# Dist_board__1_21.net
KiCad netlist of a schematic drawn in EAGLE
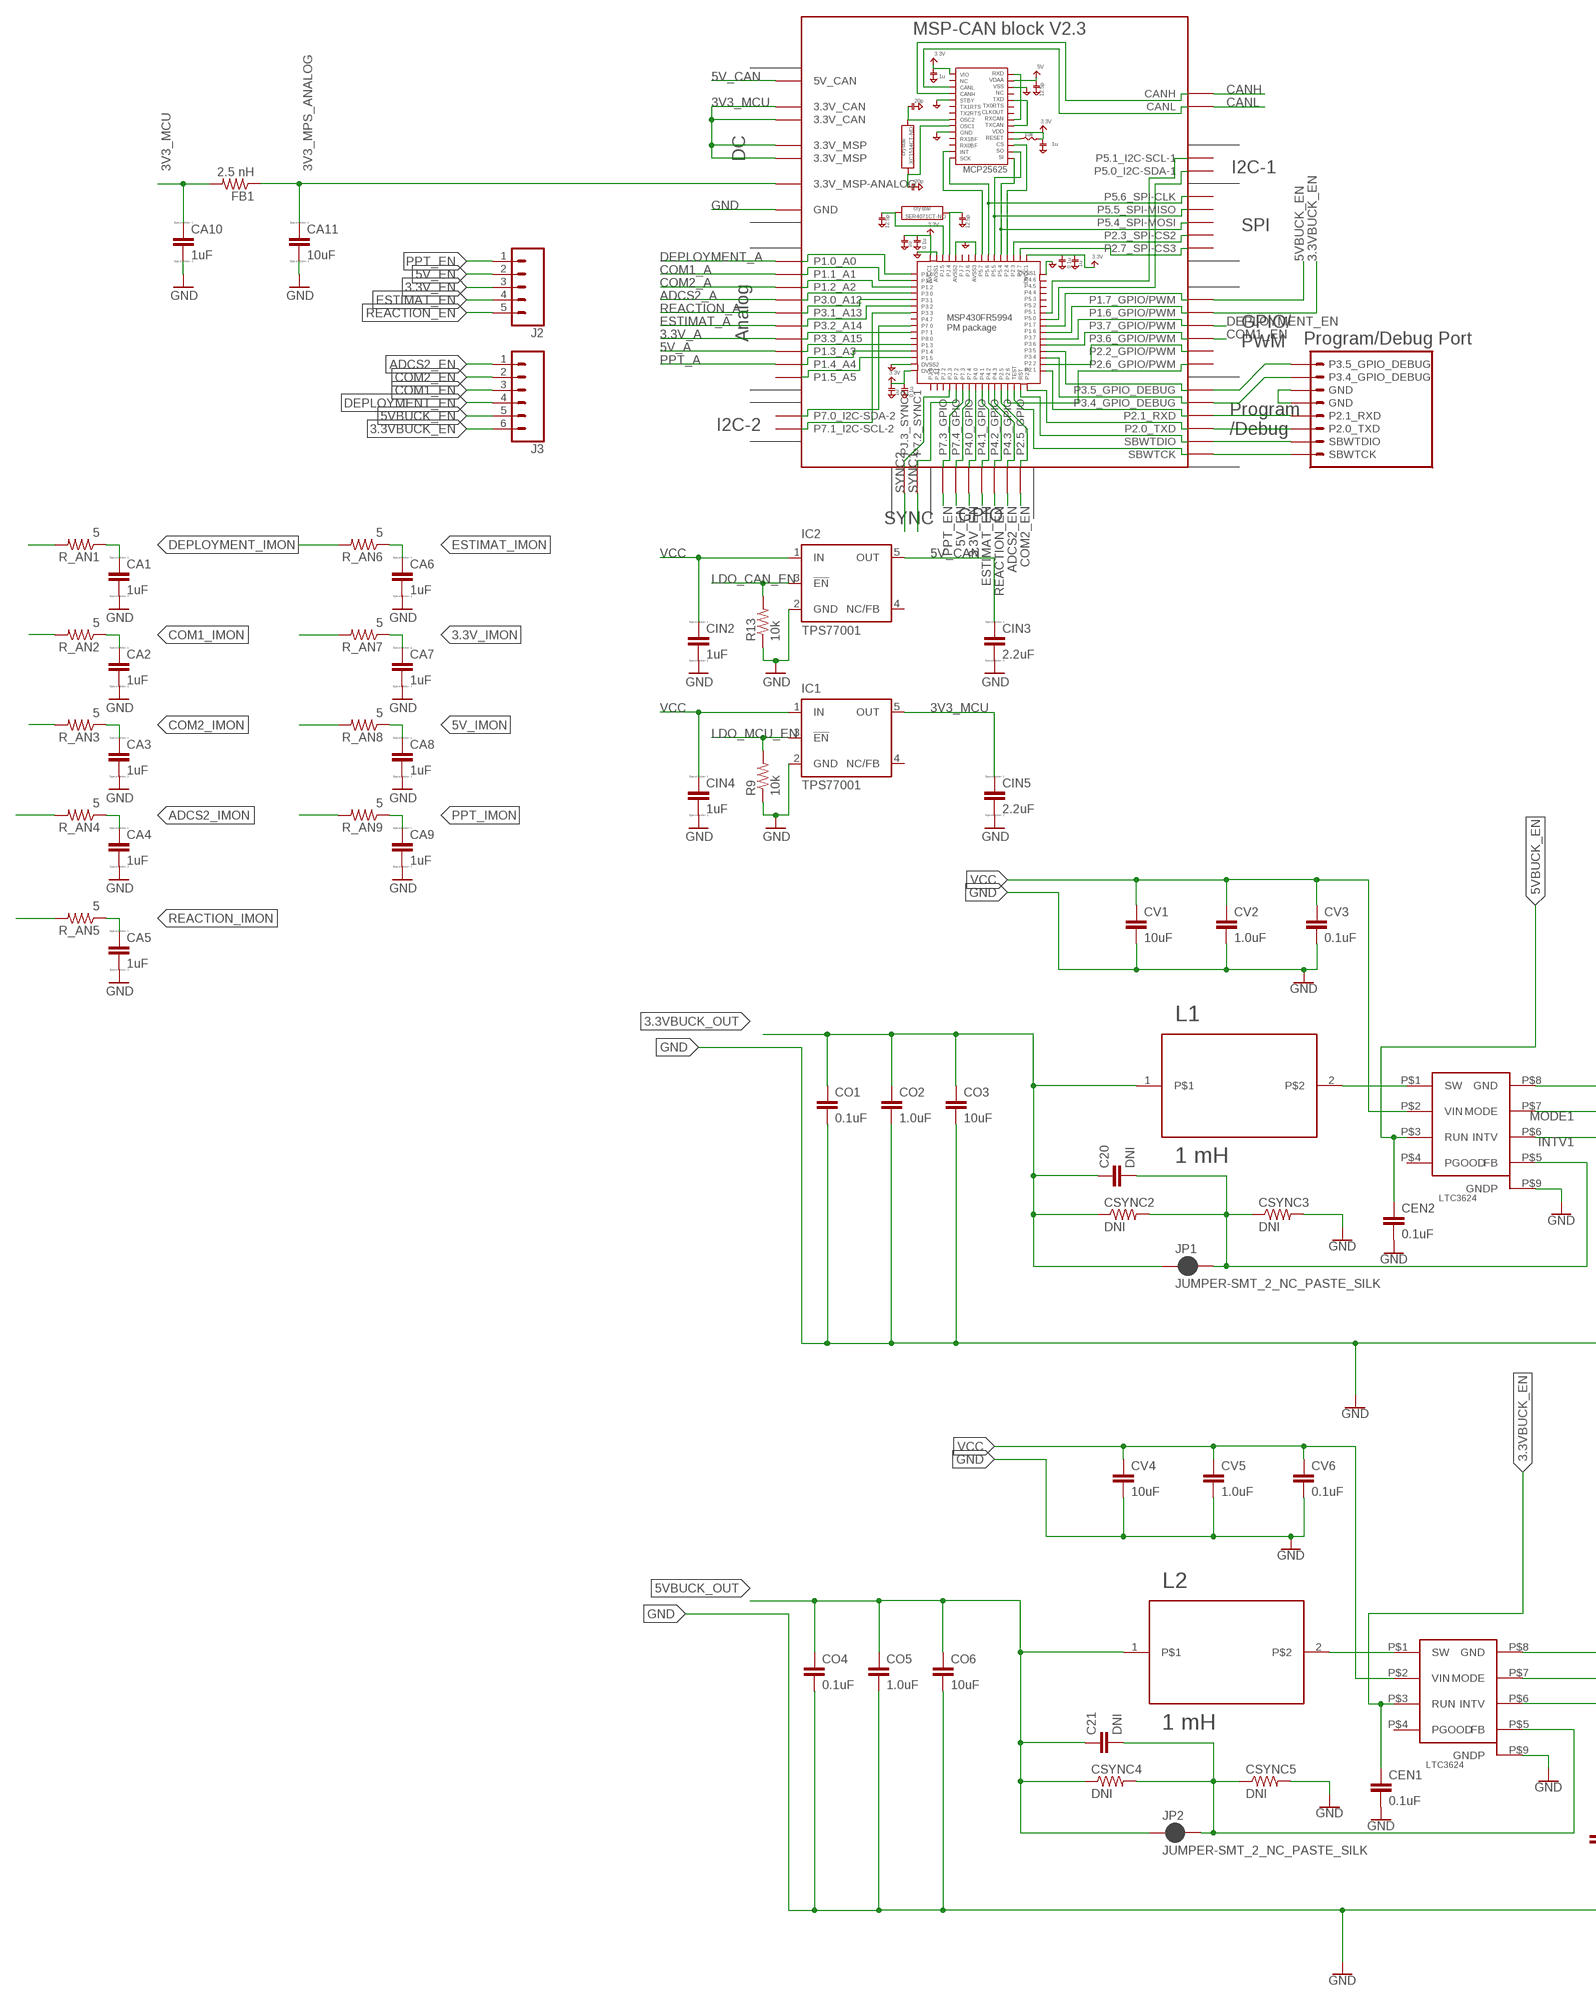
[diagram p0: schematic, sheet 1, part 1 of 3]
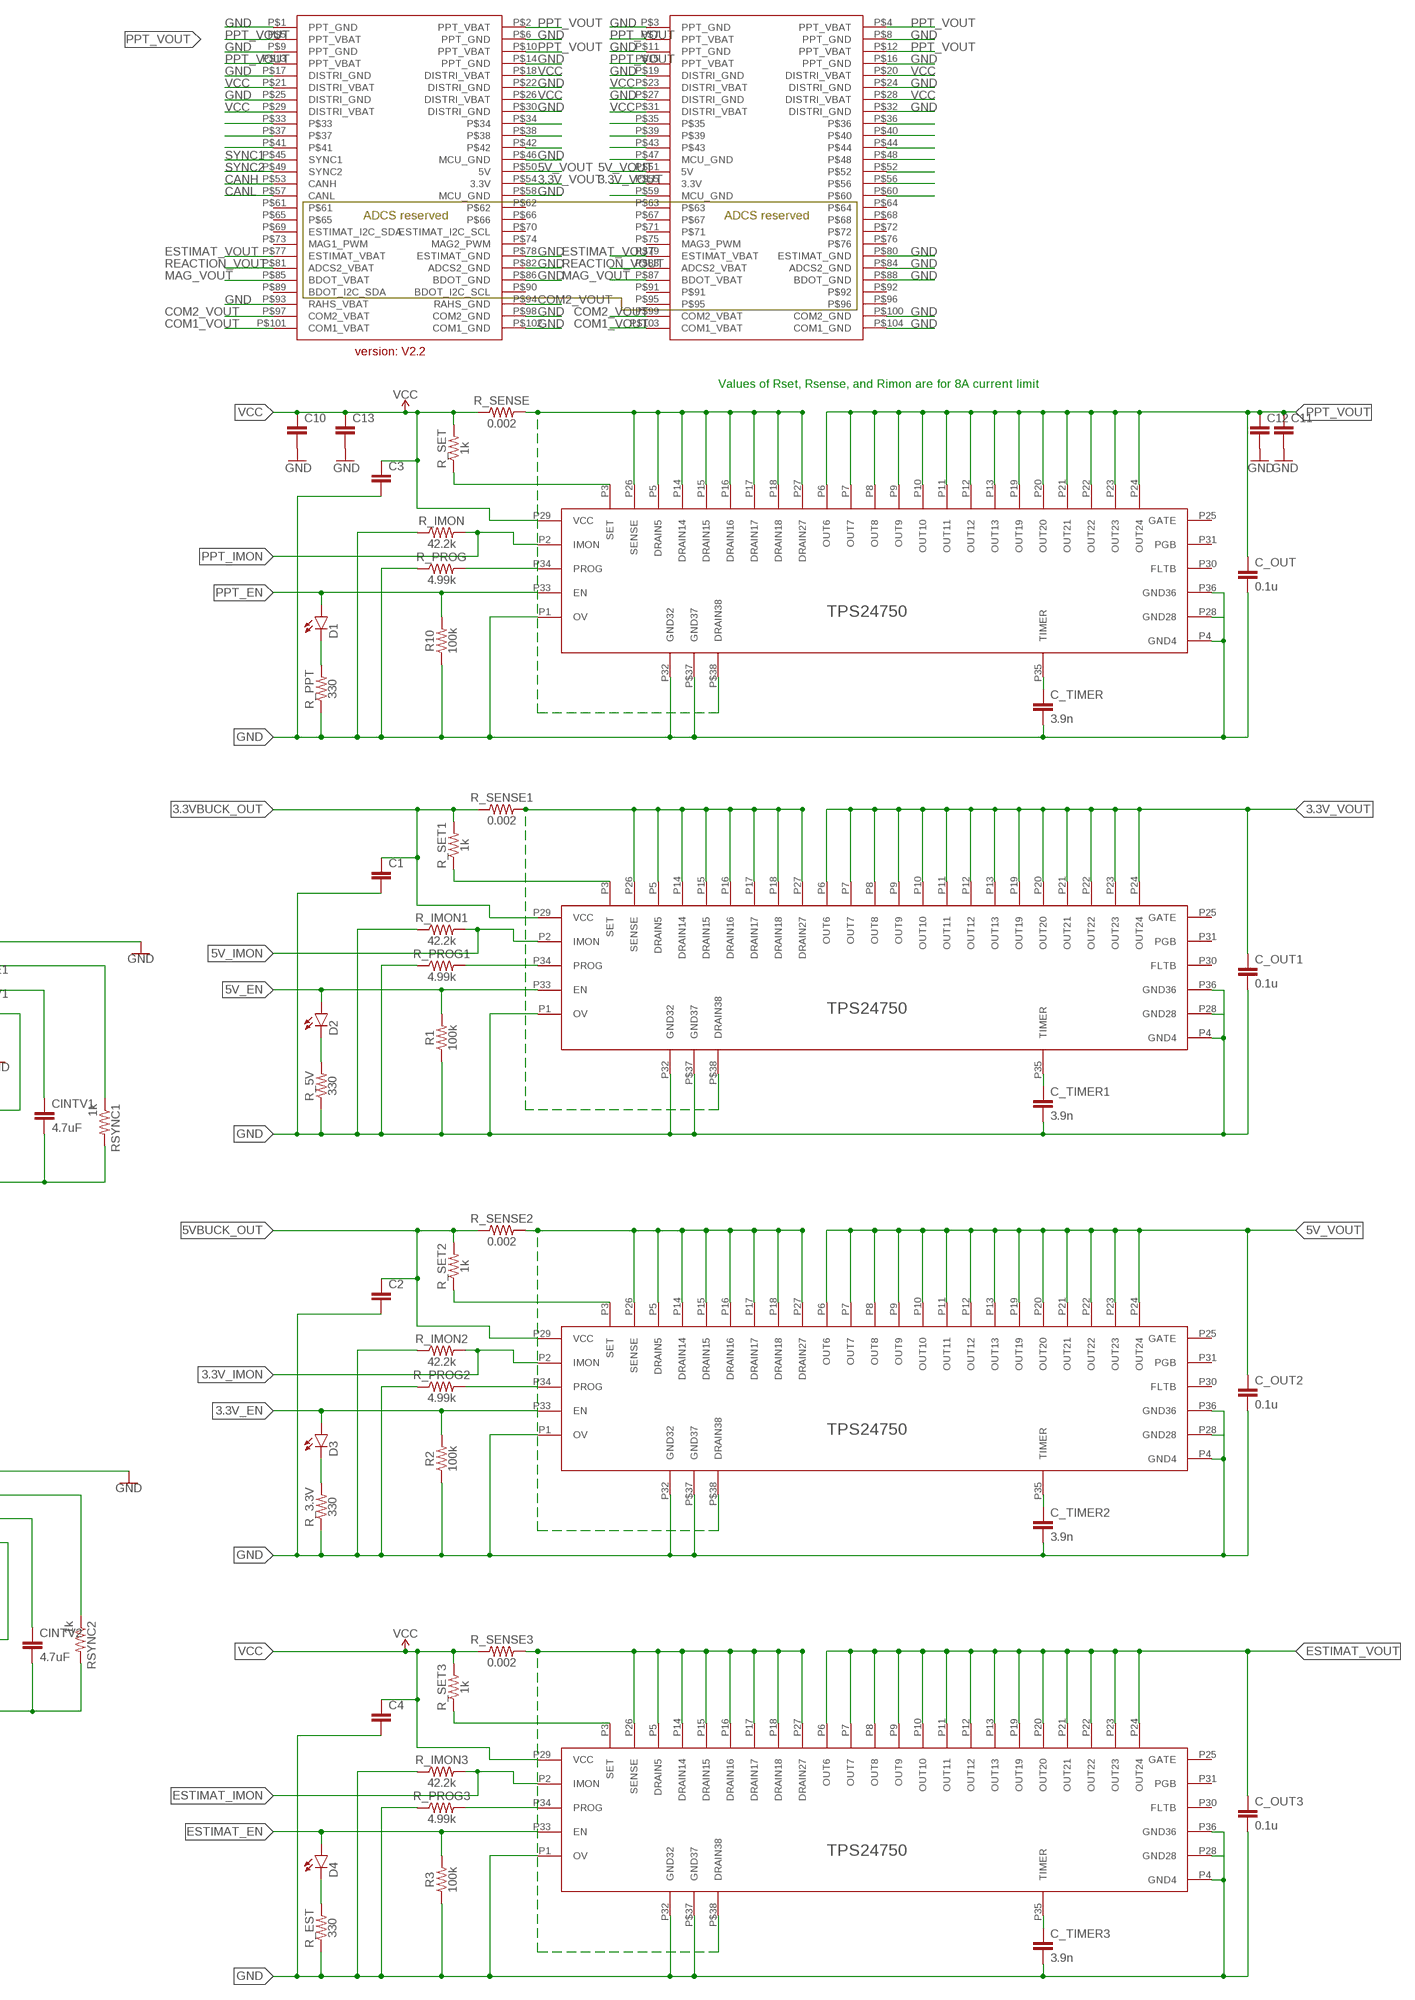
[diagram p1: schematic, sheet 1, part 2 of 3]
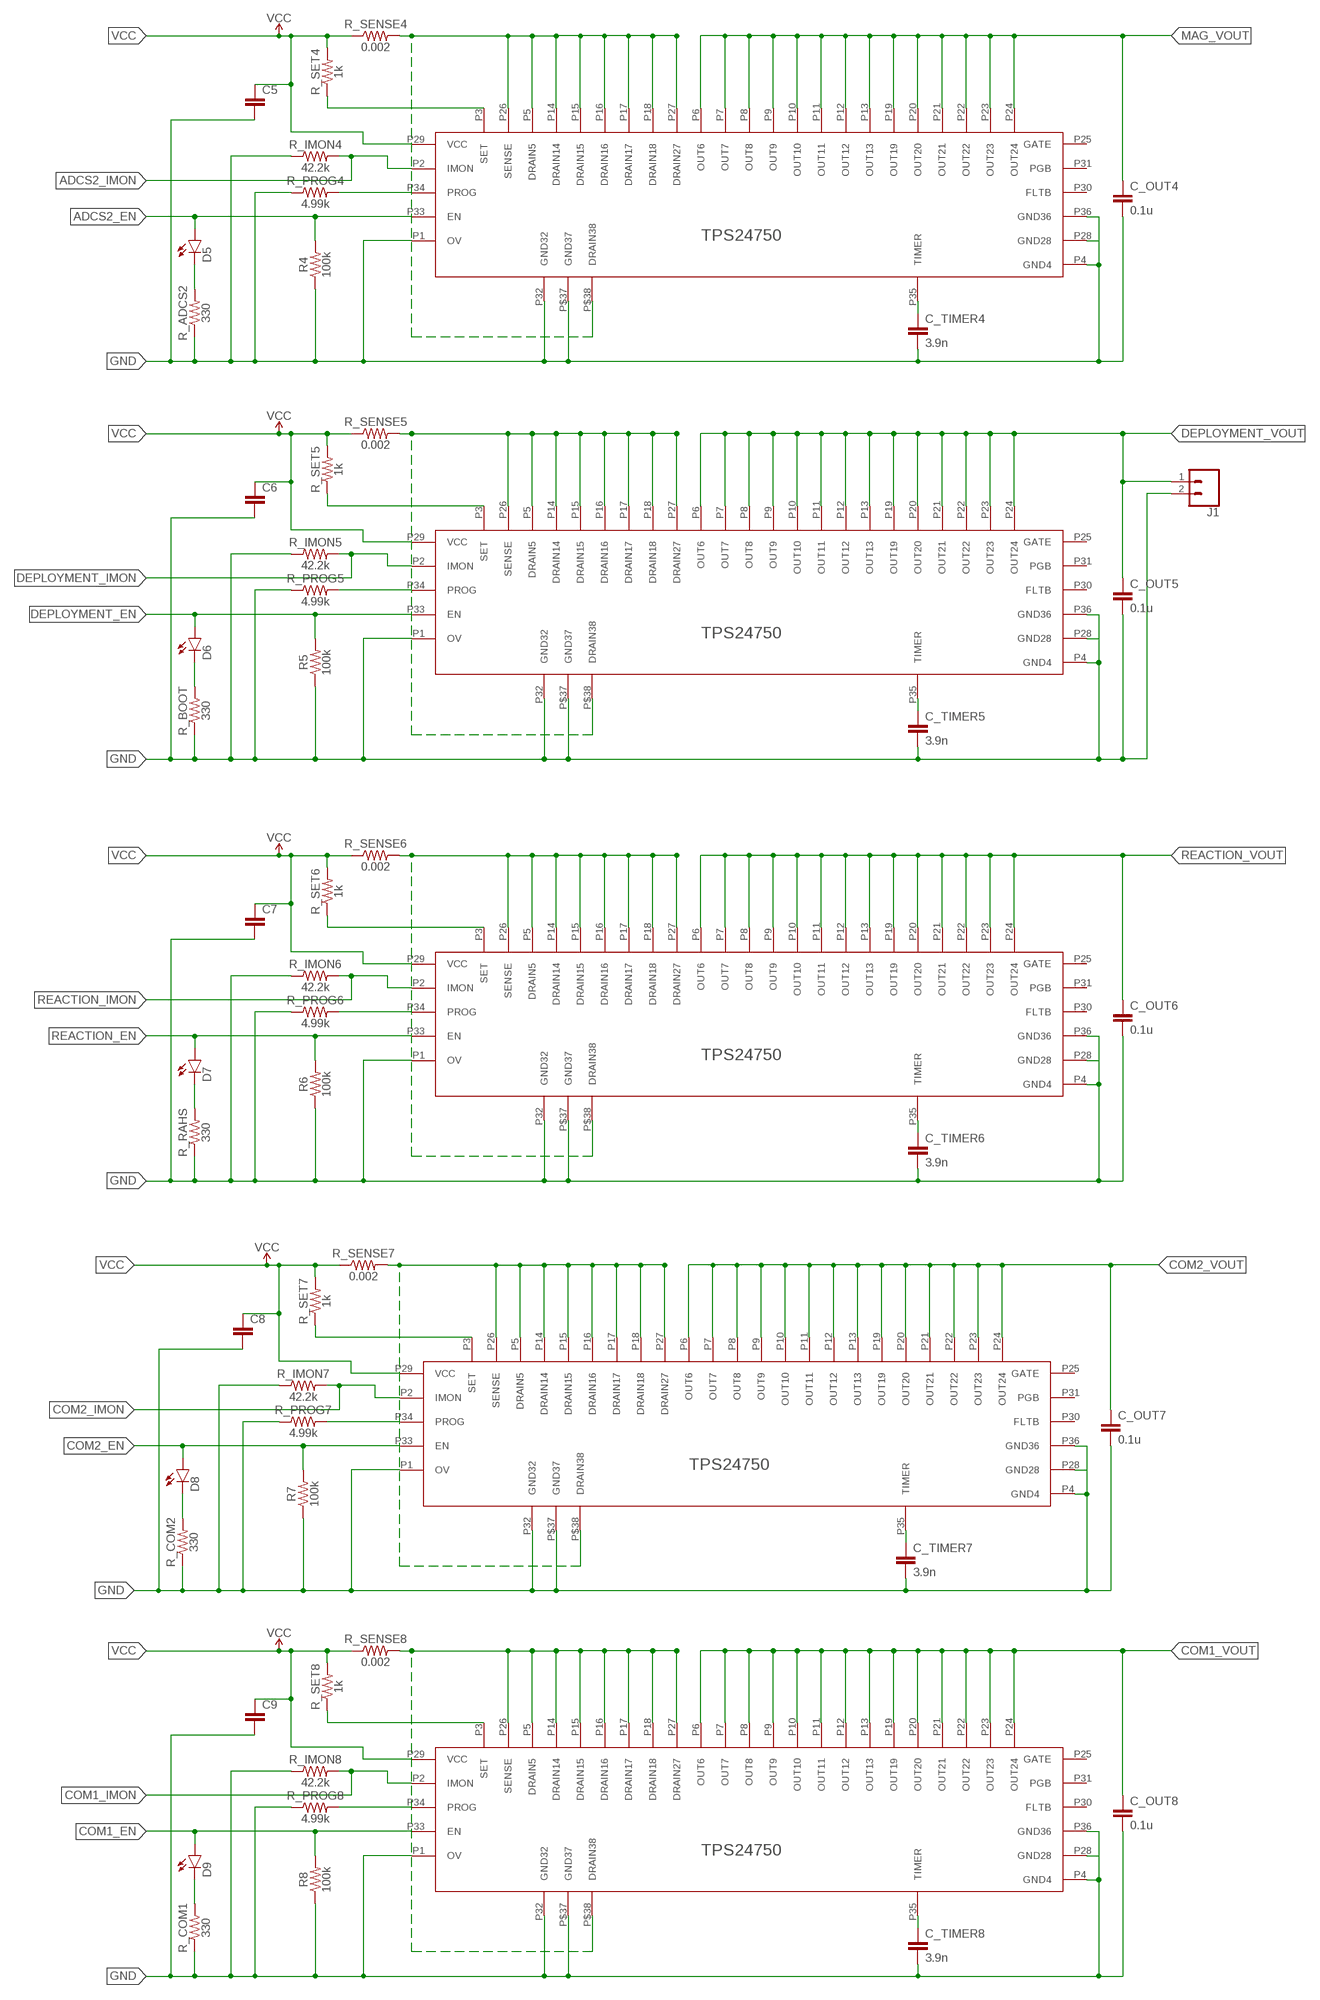
[diagram p2: schematic, sheet 1, part 3 of 3]

(export (version "E")
  (design (tool "Eeschema 10.0.6"))
  (components
    (comp (ref "C1")
      (value "GEN_CAP_0805SMD")
      (footprint "eagle-import:0805")
      (libsource (lib "eagle-import") (part "GEN_CAP_0805SMD"))
    )
    (comp (ref "C2")
      (value "GEN_CAP_0805SMD")
      (footprint "eagle-import:0805")
      (libsource (lib "eagle-import") (part "GEN_CAP_0805SMD"))
    )
    (comp (ref "C3")
      (value "GEN_CAP_0805SMD")
      (footprint "eagle-import:0805")
      (libsource (lib "eagle-import") (part "GEN_CAP_0805SMD"))
    )
    (comp (ref "C4")
      (value "GEN_CAP_0805SMD")
      (footprint "eagle-import:0805")
      (libsource (lib "eagle-import") (part "GEN_CAP_0805SMD"))
    )
    (comp (ref "C5")
      (value "GEN_CAP_0805SMD")
      (footprint "eagle-import:0805")
      (libsource (lib "eagle-import") (part "GEN_CAP_0805SMD"))
    )
    (comp (ref "C6")
      (value "GEN_CAP_0805SMD")
      (footprint "eagle-import:0805")
      (libsource (lib "eagle-import") (part "GEN_CAP_0805SMD"))
    )
    (comp (ref "C7")
      (value "GEN_CAP_0805SMD")
      (footprint "eagle-import:0805")
      (libsource (lib "eagle-import") (part "GEN_CAP_0805SMD"))
    )
    (comp (ref "C8")
      (value "GEN_CAP_0805SMD")
      (footprint "eagle-import:0805")
      (libsource (lib "eagle-import") (part "GEN_CAP_0805SMD"))
    )
    (comp (ref "C9")
      (value "GEN_CAP_0805SMD")
      (footprint "eagle-import:0805")
      (libsource (lib "eagle-import") (part "GEN_CAP_0805SMD"))
    )
    (comp (ref "C10")
      (value "GEN_CAP_0805SMD")
      (footprint "eagle-import:0805")
      (libsource (lib "eagle-import") (part "GEN_CAP_0805SMD"))
    )
    (comp (ref "C11")
      (value "GEN_CAP_0805SMD")
      (footprint "eagle-import:0805")
      (libsource (lib "eagle-import") (part "GEN_CAP_0805SMD"))
    )
    (comp (ref "C12")
      (value "GEN_CAP_0805SMD")
      (footprint "eagle-import:0805")
      (libsource (lib "eagle-import") (part "GEN_CAP_0805SMD"))
    )
    (comp (ref "C13")
      (value "GEN_CAP_0805SMD")
      (footprint "eagle-import:0805")
      (libsource (lib "eagle-import") (part "GEN_CAP_0805SMD"))
    )
    (comp (ref "C20")
      (value "DNI")
      (footprint "eagle-import:0805")
      (libsource (lib "eagle-import") (part "1.0UF-0805-25V-(+80/-20%)"))
    )
    (comp (ref "C21")
      (value "DNI")
      (footprint "eagle-import:0805")
      (libsource (lib "eagle-import") (part "1.0UF-0805-25V-(+80/-20%)"))
    )
    (comp (ref "CA1")
      (value "1uF")
      (footprint "eagle-import:C0805")
      (libsource (lib "eagle-import") (part "C"))
    )
    (comp (ref "CA2")
      (value "1uF")
      (footprint "eagle-import:C0805")
      (libsource (lib "eagle-import") (part "C"))
    )
    (comp (ref "CA3")
      (value "1uF")
      (footprint "eagle-import:C0805")
      (libsource (lib "eagle-import") (part "C"))
    )
    (comp (ref "CA4")
      (value "1uF")
      (footprint "eagle-import:C0805")
      (libsource (lib "eagle-import") (part "C"))
    )
    (comp (ref "CA5")
      (value "1uF")
      (footprint "eagle-import:C0805")
      (libsource (lib "eagle-import") (part "C"))
    )
    (comp (ref "CA6")
      (value "1uF")
      (footprint "eagle-import:C0805")
      (libsource (lib "eagle-import") (part "C"))
    )
    (comp (ref "CA7")
      (value "1uF")
      (footprint "eagle-import:C0805")
      (libsource (lib "eagle-import") (part "C"))
    )
    (comp (ref "CA8")
      (value "1uF")
      (footprint "eagle-import:C0805")
      (libsource (lib "eagle-import") (part "C"))
    )
    (comp (ref "CA9")
      (value "1uF")
      (footprint "eagle-import:C0805")
      (libsource (lib "eagle-import") (part "C"))
    )
    (comp (ref "CA10")
      (value "1uF")
      (footprint "eagle-import:C0805")
      (libsource (lib "eagle-import") (part "C"))
    )
    (comp (ref "CA11")
      (value "10uF")
      (footprint "eagle-import:C0805")
      (libsource (lib "eagle-import") (part "C"))
    )
    (comp (ref "CEN1")
      (value "0.1uF")
      (footprint "eagle-import:0805")
      (libsource (lib "eagle-import") (part "2.2UF-0805-25V-(+80/-20%)"))
    )
    (comp (ref "CEN2")
      (value "0.1uF")
      (footprint "eagle-import:0805")
      (libsource (lib "eagle-import") (part "2.2UF-0805-25V-(+80/-20%)"))
    )
    (comp (ref "CIN2")
      (value "1uF")
      (footprint "eagle-import:C0805")
      (libsource (lib "eagle-import") (part "C"))
    )
    (comp (ref "CIN3")
      (value "2.2uF")
      (footprint "eagle-import:C0805")
      (libsource (lib "eagle-import") (part "C"))
    )
    (comp (ref "CIN4")
      (value "1uF")
      (footprint "eagle-import:C0805")
      (libsource (lib "eagle-import") (part "C"))
    )
    (comp (ref "CIN5")
      (value "2.2uF")
      (footprint "eagle-import:C0805")
      (libsource (lib "eagle-import") (part "C"))
    )
    (comp (ref "CINTV1")
      (value "4.7uF")
      (footprint "eagle-import:0805")
      (libsource (lib "eagle-import") (part "2.2UF-0805-25V-(+80/-20%)"))
    )
    (comp (ref "CINTV2")
      (value "4.7uF")
      (footprint "eagle-import:0805")
      (libsource (lib "eagle-import") (part "2.2UF-0805-25V-(+80/-20%)"))
    )
    (comp (ref "CO1")
      (value "0.1uF")
      (footprint "eagle-import:0805")
      (libsource (lib "eagle-import") (part "1.0UF-0805-25V-(+80/-20%)"))
    )
    (comp (ref "CO2")
      (value "1.0uF")
      (footprint "eagle-import:0805")
      (libsource (lib "eagle-import") (part "1.0UF-0805-25V-(+80/-20%)"))
    )
    (comp (ref "CO3")
      (value "10uF")
      (footprint "eagle-import:0805")
      (libsource (lib "eagle-import") (part "10UF-0805-10V-10%"))
    )
    (comp (ref "CO4")
      (value "0.1uF")
      (footprint "eagle-import:0805")
      (libsource (lib "eagle-import") (part "1.0UF-0805-25V-(+80/-20%)"))
    )
    (comp (ref "CO5")
      (value "1.0uF")
      (footprint "eagle-import:0805")
      (libsource (lib "eagle-import") (part "1.0UF-0805-25V-(+80/-20%)"))
    )
    (comp (ref "CO6")
      (value "10uF")
      (footprint "eagle-import:0805")
      (libsource (lib "eagle-import") (part "10UF-0805-10V-10%"))
    )
    (comp (ref "CSYNC2")
      (value "DNI")
      (footprint "eagle-import:R0805")
      (libsource (lib "eagle-import") (part "R-US_R0805"))
    )
    (comp (ref "CSYNC3")
      (value "DNI")
      (footprint "eagle-import:R0805")
      (libsource (lib "eagle-import") (part "R-US_R0805"))
    )
    (comp (ref "CSYNC4")
      (value "DNI")
      (footprint "eagle-import:R0805")
      (libsource (lib "eagle-import") (part "R-US_R0805"))
    )
    (comp (ref "CSYNC5")
      (value "DNI")
      (footprint "eagle-import:R0805")
      (libsource (lib "eagle-import") (part "R-US_R0805"))
    )
    (comp (ref "CV1")
      (value "10uF")
      (footprint "eagle-import:0805")
      (libsource (lib "eagle-import") (part "1.0UF-0805-25V-10%"))
    )
    (comp (ref "CV2")
      (value "1.0uF")
      (footprint "eagle-import:0805")
      (libsource (lib "eagle-import") (part "1.0UF-0805-25V-10%"))
    )
    (comp (ref "CV3")
      (value "0.1uF")
      (footprint "eagle-import:0805")
      (libsource (lib "eagle-import") (part "1.0UF-0805-25V-10%"))
    )
    (comp (ref "CV4")
      (value "10uF")
      (footprint "eagle-import:0805")
      (libsource (lib "eagle-import") (part "1.0UF-0805-25V-10%"))
    )
    (comp (ref "CV5")
      (value "1.0uF")
      (footprint "eagle-import:0805")
      (libsource (lib "eagle-import") (part "1.0UF-0805-25V-10%"))
    )
    (comp (ref "CV6")
      (value "0.1uF")
      (footprint "eagle-import:0805")
      (libsource (lib "eagle-import") (part "1.0UF-0805-25V-10%"))
    )
    (comp (ref "C_OUT")
      (value "0.1u")
      (footprint "eagle-import:0805")
      (libsource (lib "eagle-import") (part "GEN_CAP_0805SMD"))
    )
    (comp (ref "C_OUT1")
      (value "0.1u")
      (footprint "eagle-import:0805")
      (libsource (lib "eagle-import") (part "GEN_CAP_0805SMD"))
    )
    (comp (ref "C_OUT2")
      (value "0.1u")
      (footprint "eagle-import:0805")
      (libsource (lib "eagle-import") (part "GEN_CAP_0805SMD"))
    )
    (comp (ref "C_OUT3")
      (value "0.1u")
      (footprint "eagle-import:0805")
      (libsource (lib "eagle-import") (part "GEN_CAP_0805SMD"))
    )
    (comp (ref "C_OUT4")
      (value "0.1u")
      (footprint "eagle-import:0805")
      (libsource (lib "eagle-import") (part "GEN_CAP_0805SMD"))
    )
    (comp (ref "C_OUT5")
      (value "0.1u")
      (footprint "eagle-import:0805")
      (libsource (lib "eagle-import") (part "GEN_CAP_0805SMD"))
    )
    (comp (ref "C_OUT6")
      (value "0.1u")
      (footprint "eagle-import:0805")
      (libsource (lib "eagle-import") (part "GEN_CAP_0805SMD"))
    )
    (comp (ref "C_OUT7")
      (value "0.1u")
      (footprint "eagle-import:0805")
      (libsource (lib "eagle-import") (part "GEN_CAP_0805SMD"))
    )
    (comp (ref "C_OUT8")
      (value "0.1u")
      (footprint "eagle-import:0805")
      (libsource (lib "eagle-import") (part "GEN_CAP_0805SMD"))
    )
    (comp (ref "C_TIMER")
      (value "3.9n")
      (footprint "eagle-import:0805")
      (libsource (lib "eagle-import") (part "GEN_CAP_0805SMD"))
    )
    (comp (ref "C_TIMER1")
      (value "3.9n")
      (footprint "eagle-import:0805")
      (libsource (lib "eagle-import") (part "GEN_CAP_0805SMD"))
    )
    (comp (ref "C_TIMER2")
      (value "3.9n")
      (footprint "eagle-import:0805")
      (libsource (lib "eagle-import") (part "GEN_CAP_0805SMD"))
    )
    (comp (ref "C_TIMER3")
      (value "3.9n")
      (footprint "eagle-import:0805")
      (libsource (lib "eagle-import") (part "GEN_CAP_0805SMD"))
    )
    (comp (ref "C_TIMER4")
      (value "3.9n")
      (footprint "eagle-import:0805")
      (libsource (lib "eagle-import") (part "GEN_CAP_0805SMD"))
    )
    (comp (ref "C_TIMER5")
      (value "3.9n")
      (footprint "eagle-import:0805")
      (libsource (lib "eagle-import") (part "GEN_CAP_0805SMD"))
    )
    (comp (ref "C_TIMER6")
      (value "3.9n")
      (footprint "eagle-import:0805")
      (libsource (lib "eagle-import") (part "GEN_CAP_0805SMD"))
    )
    (comp (ref "C_TIMER7")
      (value "3.9n")
      (footprint "eagle-import:0805")
      (libsource (lib "eagle-import") (part "GEN_CAP_0805SMD"))
    )
    (comp (ref "C_TIMER8")
      (value "3.9n")
      (footprint "eagle-import:0805")
      (libsource (lib "eagle-import") (part "GEN_CAP_0805SMD"))
    )
    (comp (ref "D1")
      (value "LED")
      (footprint "eagle-import:LED-1206")
      (libsource (lib "eagle-import") (part "LED"))
    )
    (comp (ref "D2")
      (value "LED")
      (footprint "eagle-import:LED-1206")
      (libsource (lib "eagle-import") (part "LED"))
    )
    (comp (ref "D3")
      (value "LED")
      (footprint "eagle-import:LED-1206")
      (libsource (lib "eagle-import") (part "LED"))
    )
    (comp (ref "D4")
      (value "LED")
      (footprint "eagle-import:LED-1206")
      (libsource (lib "eagle-import") (part "LED"))
    )
    (comp (ref "D5")
      (value "LED")
      (footprint "eagle-import:LED-1206")
      (libsource (lib "eagle-import") (part "LED"))
    )
    (comp (ref "D6")
      (value "LED")
      (footprint "eagle-import:LED-1206")
      (libsource (lib "eagle-import") (part "LED"))
    )
    (comp (ref "D7")
      (value "LED")
      (footprint "eagle-import:LED-1206")
      (libsource (lib "eagle-import") (part "LED"))
    )
    (comp (ref "D8")
      (value "LED")
      (footprint "eagle-import:LED-1206")
      (libsource (lib "eagle-import") (part "LED"))
    )
    (comp (ref "D9")
      (value "LED")
      (footprint "eagle-import:LED-1206")
      (libsource (lib "eagle-import") (part "LED"))
    )
    (comp (ref "FB1")
      (value "2.5 nH")
      (footprint "eagle-import:R0805")
      (libsource (lib "eagle-import") (part "R-US_R0805"))
    )
    (comp (ref "IC1")
      (value "TPS77001")
      (footprint "eagle-import:SOT23-DBV")
      (fields (field (name "MF") "TEXAS INSTRUMENTS") (field (name "MPN") "TPS77001DBVT"))
      (libsource (lib "eagle-import") (part "TPS77001"))
    )
    (comp (ref "IC2")
      (value "TPS77001")
      (footprint "eagle-import:SOT23-DBV")
      (fields (field (name "MF") "TEXAS INSTRUMENTS") (field (name "MPN") "TPS77001DBVT"))
      (libsource (lib "eagle-import") (part "TPS77001"))
    )
    (comp (ref "J1")
      (value "CONN_023.5MM")
      (footprint "eagle-import:SCREWTERMINAL-3.5MM-2")
      (libsource (lib "eagle-import") (part "CONN_023.5MM"))
    )
    (comp (ref "J2")
      (value "CONN_05LOCK")
      (footprint "eagle-import:1X05_LOCK")
      (libsource (lib "eagle-import") (part "CONN_05LOCK"))
    )
    (comp (ref "J3")
      (value "CONN_06LOCK")
      (footprint "eagle-import:1X06_LOCK")
      (libsource (lib "eagle-import") (part "CONN_06LOCK"))
    )
    (comp (ref "JP1")
      (value "JUMPER-SMT_2_NC_PASTE_SILK")
      (footprint "eagle-import:SMT-JUMPER_2_NC_PASTE_SILK")
      (libsource (lib "eagle-import") (part "JUMPER-SMT_2_NC_PASTE_SILK"))
    )
    (comp (ref "JP2")
      (value "JUMPER-SMT_2_NC_PASTE_SILK")
      (footprint "eagle-import:SMT-JUMPER_2_NC_PASTE_SILK")
      (libsource (lib "eagle-import") (part "JUMPER-SMT_2_NC_PASTE_SILK"))
    )
    (comp (ref "L1")
      (value "1 mH")
      (footprint "eagle-import:COILCRAFT")
      (libsource (lib "eagle-import") (part "XAL4030-332ME"))
    )
    (comp (ref "L2")
      (value "1 mH")
      (footprint "eagle-import:COILCRAFT")
      (libsource (lib "eagle-import") (part "XAL4030-332ME"))
    )
    (comp (ref "R1")
      (value "100k")
      (footprint "eagle-import:0805")
      (libsource (lib "eagle-import") (part "GEN_RES_0805SMD"))
    )
    (comp (ref "R2")
      (value "100k")
      (footprint "eagle-import:0805")
      (libsource (lib "eagle-import") (part "GEN_RES_0805SMD"))
    )
    (comp (ref "R3")
      (value "100k")
      (footprint "eagle-import:0805")
      (libsource (lib "eagle-import") (part "GEN_RES_0805SMD"))
    )
    (comp (ref "R4")
      (value "100k")
      (footprint "eagle-import:0805")
      (libsource (lib "eagle-import") (part "GEN_RES_0805SMD"))
    )
    (comp (ref "R5")
      (value "100k")
      (footprint "eagle-import:0805")
      (libsource (lib "eagle-import") (part "GEN_RES_0805SMD"))
    )
    (comp (ref "R6")
      (value "100k")
      (footprint "eagle-import:0805")
      (libsource (lib "eagle-import") (part "GEN_RES_0805SMD"))
    )
    (comp (ref "R7")
      (value "100k")
      (footprint "eagle-import:0805")
      (libsource (lib "eagle-import") (part "GEN_RES_0805SMD"))
    )
    (comp (ref "R8")
      (value "100k")
      (footprint "eagle-import:0805")
      (libsource (lib "eagle-import") (part "GEN_RES_0805SMD"))
    )
    (comp (ref "R9")
      (value "10k")
      (footprint "eagle-import:R0805")
      (libsource (lib "eagle-import") (part "R-US_R0805"))
    )
    (comp (ref "R10")
      (value "100k")
      (footprint "eagle-import:0805")
      (libsource (lib "eagle-import") (part "GEN_RES_0805SMD"))
    )
    (comp (ref "R13")
      (value "10k")
      (footprint "eagle-import:R0805")
      (libsource (lib "eagle-import") (part "R-US_R0805"))
    )
    (comp (ref "RSYNC1")
      (value "1k")
      (footprint "eagle-import:R0805")
      (libsource (lib "eagle-import") (part "R-US_R0805"))
    )
    (comp (ref "RSYNC2")
      (value "1k")
      (footprint "eagle-import:R0805")
      (libsource (lib "eagle-import") (part "R-US_R0805"))
    )
    (comp (ref "R_3.3V")
      (value "330")
      (footprint "eagle-import:0805")
      (libsource (lib "eagle-import") (part "GEN_RES_0805SMD"))
    )
    (comp (ref "R_5V")
      (value "330")
      (footprint "eagle-import:0805")
      (libsource (lib "eagle-import") (part "GEN_RES_0805SMD"))
    )
    (comp (ref "R_ADCS2")
      (value "330")
      (footprint "eagle-import:0805")
      (libsource (lib "eagle-import") (part "GEN_RES_0805SMD"))
    )
    (comp (ref "R_AN1")
      (value "5")
      (footprint "eagle-import:R0805")
      (libsource (lib "eagle-import") (part "R-US_R0805"))
    )
    (comp (ref "R_AN2")
      (value "5")
      (footprint "eagle-import:R0805")
      (libsource (lib "eagle-import") (part "R-US_R0805"))
    )
    (comp (ref "R_AN3")
      (value "5")
      (footprint "eagle-import:R0805")
      (libsource (lib "eagle-import") (part "R-US_R0805"))
    )
    (comp (ref "R_AN4")
      (value "5")
      (footprint "eagle-import:R0805")
      (libsource (lib "eagle-import") (part "R-US_R0805"))
    )
    (comp (ref "R_AN5")
      (value "5")
      (footprint "eagle-import:R0805")
      (libsource (lib "eagle-import") (part "R-US_R0805"))
    )
    (comp (ref "R_AN6")
      (value "5")
      (footprint "eagle-import:R0805")
      (libsource (lib "eagle-import") (part "R-US_R0805"))
    )
    (comp (ref "R_AN7")
      (value "5")
      (footprint "eagle-import:R0805")
      (libsource (lib "eagle-import") (part "R-US_R0805"))
    )
    (comp (ref "R_AN8")
      (value "5")
      (footprint "eagle-import:R0805")
      (libsource (lib "eagle-import") (part "R-US_R0805"))
    )
    (comp (ref "R_AN9")
      (value "5")
      (footprint "eagle-import:R0805")
      (libsource (lib "eagle-import") (part "R-US_R0805"))
    )
    (comp (ref "R_BOOT")
      (value "330")
      (footprint "eagle-import:0805")
      (libsource (lib "eagle-import") (part "GEN_RES_0805SMD"))
    )
    (comp (ref "R_COM1")
      (value "330")
      (footprint "eagle-import:0805")
      (libsource (lib "eagle-import") (part "GEN_RES_0805SMD"))
    )
    (comp (ref "R_COM2")
      (value "330")
      (footprint "eagle-import:0805")
      (libsource (lib "eagle-import") (part "GEN_RES_0805SMD"))
    )
    (comp (ref "R_EST")
      (value "330")
      (footprint "eagle-import:0805")
      (libsource (lib "eagle-import") (part "GEN_RES_0805SMD"))
    )
    (comp (ref "R_IMON")
      (value "42.2k")
      (footprint "eagle-import:0805")
      (libsource (lib "eagle-import") (part "GEN_RES_0805SMD"))
    )
    (comp (ref "R_IMON1")
      (value "42.2k")
      (footprint "eagle-import:0805")
      (libsource (lib "eagle-import") (part "GEN_RES_0805SMD"))
    )
    (comp (ref "R_IMON2")
      (value "42.2k")
      (footprint "eagle-import:0805")
      (libsource (lib "eagle-import") (part "GEN_RES_0805SMD"))
    )
    (comp (ref "R_IMON3")
      (value "42.2k")
      (footprint "eagle-import:0805")
      (libsource (lib "eagle-import") (part "GEN_RES_0805SMD"))
    )
    (comp (ref "R_IMON4")
      (value "42.2k")
      (footprint "eagle-import:0805")
      (libsource (lib "eagle-import") (part "GEN_RES_0805SMD"))
    )
    (comp (ref "R_IMON5")
      (value "42.2k")
      (footprint "eagle-import:0805")
      (libsource (lib "eagle-import") (part "GEN_RES_0805SMD"))
    )
    (comp (ref "R_IMON6")
      (value "42.2k")
      (footprint "eagle-import:0805")
      (libsource (lib "eagle-import") (part "GEN_RES_0805SMD"))
    )
    (comp (ref "R_IMON7")
      (value "42.2k")
      (footprint "eagle-import:0805")
      (libsource (lib "eagle-import") (part "GEN_RES_0805SMD"))
    )
    (comp (ref "R_IMON8")
      (value "42.2k")
      (footprint "eagle-import:0805")
      (libsource (lib "eagle-import") (part "GEN_RES_0805SMD"))
    )
    (comp (ref "R_PPT")
      (value "330")
      (footprint "eagle-import:0805")
      (libsource (lib "eagle-import") (part "GEN_RES_0805SMD"))
    )
    (comp (ref "R_PROG")
      (value "4.99k")
      (footprint "eagle-import:0805")
      (libsource (lib "eagle-import") (part "GEN_RES_0805SMD"))
    )
    (comp (ref "R_PROG1")
      (value "4.99k")
      (footprint "eagle-import:0805")
      (libsource (lib "eagle-import") (part "GEN_RES_0805SMD"))
    )
    (comp (ref "R_PROG2")
      (value "4.99k")
      (footprint "eagle-import:0805")
      (libsource (lib "eagle-import") (part "GEN_RES_0805SMD"))
    )
    (comp (ref "R_PROG3")
      (value "4.99k")
      (footprint "eagle-import:0805")
      (libsource (lib "eagle-import") (part "GEN_RES_0805SMD"))
    )
    (comp (ref "R_PROG4")
      (value "4.99k")
      (footprint "eagle-import:0805")
      (libsource (lib "eagle-import") (part "GEN_RES_0805SMD"))
    )
    (comp (ref "R_PROG5")
      (value "4.99k")
      (footprint "eagle-import:0805")
      (libsource (lib "eagle-import") (part "GEN_RES_0805SMD"))
    )
    (comp (ref "R_PROG6")
      (value "4.99k")
      (footprint "eagle-import:0805")
      (libsource (lib "eagle-import") (part "GEN_RES_0805SMD"))
    )
    (comp (ref "R_PROG7")
      (value "4.99k")
      (footprint "eagle-import:0805")
      (libsource (lib "eagle-import") (part "GEN_RES_0805SMD"))
    )
    (comp (ref "R_PROG8")
      (value "4.99k")
      (footprint "eagle-import:0805")
      (libsource (lib "eagle-import") (part "GEN_RES_0805SMD"))
    )
    (comp (ref "R_RAHS")
      (value "330")
      (footprint "eagle-import:0805")
      (libsource (lib "eagle-import") (part "GEN_RES_0805SMD"))
    )
    (comp (ref "R_SENSE")
      (value "0.002")
      (footprint "eagle-import:2010")
      (libsource (lib "eagle-import") (part "GEN_RES_2010SMD"))
    )
    (comp (ref "R_SENSE1")
      (value "0.002")
      (footprint "eagle-import:2010")
      (libsource (lib "eagle-import") (part "GEN_RES_2010SMD"))
    )
    (comp (ref "R_SENSE2")
      (value "0.002")
      (footprint "eagle-import:2010")
      (libsource (lib "eagle-import") (part "GEN_RES_2010SMD"))
    )
    (comp (ref "R_SENSE3")
      (value "0.002")
      (footprint "eagle-import:2010")
      (libsource (lib "eagle-import") (part "GEN_RES_2010SMD"))
    )
    (comp (ref "R_SENSE4")
      (value "0.002")
      (footprint "eagle-import:2010")
      (libsource (lib "eagle-import") (part "GEN_RES_2010SMD"))
    )
    (comp (ref "R_SENSE5")
      (value "0.002")
      (footprint "eagle-import:2010")
      (libsource (lib "eagle-import") (part "GEN_RES_2010SMD"))
    )
    (comp (ref "R_SENSE6")
      (value "0.002")
      (footprint "eagle-import:2010")
      (libsource (lib "eagle-import") (part "GEN_RES_2010SMD"))
    )
    (comp (ref "R_SENSE7")
      (value "0.002")
      (footprint "eagle-import:2010")
      (libsource (lib "eagle-import") (part "GEN_RES_2010SMD"))
    )
    (comp (ref "R_SENSE8")
      (value "0.002")
      (footprint "eagle-import:2010")
      (libsource (lib "eagle-import") (part "GEN_RES_2010SMD"))
    )
    (comp (ref "R_SET")
      (value "1k")
      (footprint "eagle-import:0805")
      (libsource (lib "eagle-import") (part "GEN_RES_0805SMD"))
    )
    (comp (ref "R_SET1")
      (value "1k")
      (footprint "eagle-import:0805")
      (libsource (lib "eagle-import") (part "GEN_RES_0805SMD"))
    )
    (comp (ref "R_SET2")
      (value "1k")
      (footprint "eagle-import:0805")
      (libsource (lib "eagle-import") (part "GEN_RES_0805SMD"))
    )
    (comp (ref "R_SET3")
      (value "1k")
      (footprint "eagle-import:0805")
      (libsource (lib "eagle-import") (part "GEN_RES_0805SMD"))
    )
    (comp (ref "R_SET4")
      (value "1k")
      (footprint "eagle-import:0805")
      (libsource (lib "eagle-import") (part "GEN_RES_0805SMD"))
    )
    (comp (ref "R_SET5")
      (value "1k")
      (footprint "eagle-import:0805")
      (libsource (lib "eagle-import") (part "GEN_RES_0805SMD"))
    )
    (comp (ref "R_SET6")
      (value "1k")
      (footprint "eagle-import:0805")
      (libsource (lib "eagle-import") (part "GEN_RES_0805SMD"))
    )
    (comp (ref "R_SET7")
      (value "1k")
      (footprint "eagle-import:0805")
      (libsource (lib "eagle-import") (part "GEN_RES_0805SMD"))
    )
    (comp (ref "R_SET8")
      (value "1k")
      (footprint "eagle-import:0805")
      (libsource (lib "eagle-import") (part "GEN_RES_0805SMD"))
    )
    (comp (ref "U$1")
      (value "TI_SWITCH_TPS24750")
      (footprint "eagle-import:QFN-36")
      (libsource (lib "eagle-import") (part "TI_SWITCH_TPS24750"))
    )
    (comp (ref "U$2")
      (value "PC104_CONNECTOR")
      (footprint "eagle-import:PC104_CONNECTOR")
      (libsource (lib "eagle-import") (part "PC104_CONNECTOR"))
    )
    (comp (ref "U$5")
      (value "TI_SWITCH_TPS24750")
      (footprint "eagle-import:QFN-36")
      (libsource (lib "eagle-import") (part "TI_SWITCH_TPS24750"))
    )
    (comp (ref "U$6")
      (value "TI_SWITCH_TPS24750")
      (footprint "eagle-import:QFN-36")
      (libsource (lib "eagle-import") (part "TI_SWITCH_TPS24750"))
    )
    (comp (ref "U$7")
      (value "TI_SWITCH_TPS24750")
      (footprint "eagle-import:QFN-36")
      (libsource (lib "eagle-import") (part "TI_SWITCH_TPS24750"))
    )
    (comp (ref "U$8")
      (value "TI_SWITCH_TPS24750")
      (footprint "eagle-import:QFN-36")
      (libsource (lib "eagle-import") (part "TI_SWITCH_TPS24750"))
    )
    (comp (ref "U$9")
      (value "TI_SWITCH_TPS24750")
      (footprint "eagle-import:QFN-36")
      (libsource (lib "eagle-import") (part "TI_SWITCH_TPS24750"))
    )
    (comp (ref "U$10")
      (value "TI_SWITCH_TPS24750")
      (footprint "eagle-import:QFN-36")
      (libsource (lib "eagle-import") (part "TI_SWITCH_TPS24750"))
    )
    (comp (ref "U$11")
      (value "TI_SWITCH_TPS24750")
      (footprint "eagle-import:QFN-36")
      (libsource (lib "eagle-import") (part "TI_SWITCH_TPS24750"))
    )
    (comp (ref "U$12")
      (value "TI_SWITCH_TPS24750")
      (footprint "eagle-import:QFN-36")
      (libsource (lib "eagle-import") (part "TI_SWITCH_TPS24750"))
    )
    (comp (ref "U$13")
      (value "LINEAR_BUCK_LTC3624")
      (footprint "eagle-import:8-LFCSP")
      (libsource (lib "eagle-import") (part "LINEAR_BUCK_LTC3624"))
    )
    (comp (ref "U$14")
      (value "LINEAR_BUCK_LTC3624")
      (footprint "eagle-import:8-LFCSP")
      (libsource (lib "eagle-import") (part "LINEAR_BUCK_LTC3624"))
    )
    (comp (ref "U$15")
      (value "MSP-CAN_BLOCK")
      (footprint "eagle-import:MSP-CAN_BLOCK")
      (libsource (lib "eagle-import") (part "MSP-CAN_BLOCK"))
    )
    (comp (ref "U$16")
      (value "PROGRAM/DEBUG_PORT")
      (footprint "eagle-import:1X08_CONNECTOR")
      (libsource (lib "eagle-import") (part "PROGRAM/DEBUG_PORT"))
    )
  )
  (nets
    (net (code "1") (name "/3.3V_A") (class "Default")
      (node (ref "CA7") (pin "1") (pinfunction "1_1") (pintype "passive"))
      (node (ref "R_AN7") (pin "1") (pinfunction "1_1") (pintype "passive"))
      (node (ref "U$15") (pin "P3.3_A15") (pinfunction "P3.3_A15_P3.3_A15") (pintype "bidirectional"))
    )
    (net (code "2") (name "/3V3_MCU") (class "Default")
      (node (ref "CA10") (pin "1") (pinfunction "1_1") (pintype "passive"))
      (node (ref "CIN5") (pin "1") (pinfunction "1_1") (pintype "passive"))
      (node (ref "FB1") (pin "2") (pinfunction "2_2") (pintype "passive"))
      (node (ref "IC1") (pin "5") (pinfunction "OUT_5") (pintype "passive"))
      (node (ref "U$15") (pin "3.3V@CAN1") (pinfunction "3.3V_CAN_3.3V@CAN1") (pintype "bidirectional"))
      (node (ref "U$15") (pin "3.3V@CAN2") (pinfunction "3.3V_CAN_3.3V@CAN2") (pintype "bidirectional"))
      (node (ref "U$15") (pin "3.3V@MSP1") (pinfunction "3.3V_MSP_3.3V@MSP1") (pintype "bidirectional"))
      (node (ref "U$15") (pin "3.3V@MSP2") (pinfunction "3.3V_MSP_3.3V@MSP2") (pintype "bidirectional"))
    )
    (net (code "3") (name "/3V3_MPS_ANALOG") (class "Default")
      (node (ref "CA11") (pin "1") (pinfunction "1_1") (pintype "passive"))
      (node (ref "FB1") (pin "1") (pinfunction "1_1") (pintype "passive"))
      (node (ref "U$15") (pin "3.3V_ANALOG@MSP2") (pinfunction "3.3V_MSP-ANALOG_3.3V_ANALOG@MSP2") (pintype "bidirectional"))
    )
    (net (code "4") (name "/5V_A") (class "Default")
      (node (ref "CA8") (pin "1") (pinfunction "1_1") (pintype "passive"))
      (node (ref "R_AN8") (pin "1") (pinfunction "1_1") (pintype "passive"))
      (node (ref "U$15") (pin "P1.3_A3") (pinfunction "P1.3_A3_P1.3_A3") (pintype "bidirectional"))
    )
    (net (code "5") (name "/5V_CAN") (class "Default")
      (node (ref "CIN3") (pin "1") (pinfunction "1_1") (pintype "passive"))
      (node (ref "IC2") (pin "5") (pinfunction "OUT_5") (pintype "passive"))
      (node (ref "U$15") (pin "5V") (pinfunction "5V_CAN_5V") (pintype "bidirectional"))
    )
    (net (code "6") (name "/ADCS2_A") (class "Default")
      (node (ref "CA4") (pin "1") (pinfunction "1_1") (pintype "passive"))
      (node (ref "R_AN4") (pin "1") (pinfunction "1_1") (pintype "passive"))
      (node (ref "U$15") (pin "P3.0_A12") (pinfunction "P3.0_A12_P3.0_A12") (pintype "bidirectional"))
    )
    (net (code "7") (name "/CANH") (class "Default")
      (node (ref "U$15") (pin "CANH") (pinfunction "CANH_CANH") (pintype "bidirectional"))
      (node (ref "U$2") (pin "P$53") (pinfunction "CANH_P$53") (pintype "bidirectional"))
    )
    (net (code "8") (name "/CANL") (class "Default")
      (node (ref "U$15") (pin "CANL") (pinfunction "CANL_CANL") (pintype "bidirectional"))
      (node (ref "U$2") (pin "P$57") (pinfunction "CANL_P$57") (pintype "bidirectional"))
    )
    (net (code "9") (name "/COM1_A") (class "Default")
      (node (ref "CA2") (pin "1") (pinfunction "1_1") (pintype "passive"))
      (node (ref "R_AN2") (pin "1") (pinfunction "1_1") (pintype "passive"))
      (node (ref "U$15") (pin "P1.1_A1") (pinfunction "P1.1_A1_P1.1_A1") (pintype "bidirectional"))
    )
    (net (code "10") (name "/COM2_A") (class "Default")
      (node (ref "CA3") (pin "1") (pinfunction "1_1") (pintype "passive"))
      (node (ref "R_AN3") (pin "1") (pinfunction "1_1") (pintype "passive"))
      (node (ref "U$15") (pin "P1.2_A2") (pinfunction "P1.2_A2_P1.2_A2") (pintype "bidirectional"))
    )
    (net (code "11") (name "/DEPLOYMENT_A") (class "Default")
      (node (ref "CA1") (pin "1") (pinfunction "1_1") (pintype "passive"))
      (node (ref "R_AN1") (pin "1") (pinfunction "1_1") (pintype "passive"))
      (node (ref "U$15") (pin "P1.0_A0") (pinfunction "P1.0_A0_P1.0_A0") (pintype "bidirectional"))
    )
    (net (code "12") (name "/ESTIMAT_A") (class "Default")
      (node (ref "CA6") (pin "1") (pinfunction "1_1") (pintype "passive"))
      (node (ref "R_AN6") (pin "1") (pinfunction "1_1") (pintype "passive"))
      (node (ref "U$15") (pin "P3.2_A14") (pinfunction "P3.2_A14_P3.2_A14") (pintype "bidirectional"))
    )
    (net (code "13") (name "/INTV1") (class "Default")
      (node (ref "CINTV1") (pin "1") (pinfunction "1_1") (pintype "passive"))
      (node (ref "U$13") (pin "P$6") (pinfunction "INTV_P$6") (pintype "bidirectional"))
    )
    (net (code "14") (name "/LDO_CAN_EN") (class "Default")
      (node (ref "IC2") (pin "3") (pinfunction "~{EN}_3") (pintype "input"))
      (node (ref "R13") (pin "2") (pinfunction "2_2") (pintype "passive"))
    )
    (net (code "15") (name "/LDO_MCU_EN") (class "Default")
      (node (ref "IC1") (pin "3") (pinfunction "~{EN}_3") (pintype "input"))
      (node (ref "R9") (pin "2") (pinfunction "2_2") (pintype "passive"))
    )
    (net (code "16") (name "/MODE1") (class "Default")
      (node (ref "RSYNC1") (pin "1") (pinfunction "1_1") (pintype "passive"))
      (node (ref "U$13") (pin "P$7") (pinfunction "MODE_P$7") (pintype "bidirectional"))
    )
    (net (code "17") (name "/PPT_A") (class "Default")
      (node (ref "CA9") (pin "1") (pinfunction "1_1") (pintype "passive"))
      (node (ref "R_AN9") (pin "1") (pinfunction "1_1") (pintype "passive"))
      (node (ref "U$15") (pin "P1.4_A4") (pinfunction "P1.4_A4_P1.4_A4") (pintype "bidirectional"))
    )
    (net (code "18") (name "/REACTION_A") (class "Default")
      (node (ref "CA5") (pin "1") (pinfunction "1_1") (pintype "passive"))
      (node (ref "R_AN5") (pin "1") (pinfunction "1_1") (pintype "passive"))
      (node (ref "U$15") (pin "P3.1_A13") (pinfunction "P3.1_A13_P3.1_A13") (pintype "bidirectional"))
    )
    (net (code "19") (name "/SYNC1") (class "Default")
      (node (ref "U$15") (pin "P7.2_SYNC1") (pinfunction "P7.2_SYNC1_P7.2_SYNC1") (pintype "bidirectional"))
      (node (ref "U$2") (pin "P$45") (pinfunction "SYNC1_P$45") (pintype "bidirectional"))
    )
    (net (code "20") (name "/SYNC2") (class "Default")
      (node (ref "U$15") (pin "PJ.3_SYNC2") (pinfunction "PJ.3_SYNC2_PJ.3_SYNC2") (pintype "bidirectional"))
      (node (ref "U$2") (pin "P$49") (pinfunction "SYNC2_P$49") (pintype "bidirectional"))
    )
    (net (code "21") (name "3.3VBUCK_EN") (class "Default")
      (node (ref "CEN1") (pin "1") (pinfunction "1_1") (pintype "passive"))
      (node (ref "J3") (pin "6") (pinfunction "6_6") (pintype "passive"))
      (node (ref "U$14") (pin "P$3") (pinfunction "RUN_P$3") (pintype "bidirectional"))
      (node (ref "U$15") (pin "P1.6_GPIO/PWM") (pinfunction "P1.6_GPIO/PWM_P1.6_GPIO/PWM") (pintype "bidirectional"))
    )
    (net (code "22") (name "3.3VBUCK_OUT") (class "Default")
      (node (ref "C1") (pin "1") (pinfunction "1_1") (pintype "passive"))
      (node (ref "C20") (pin "1") (pinfunction "1_1") (pintype "passive"))
      (node (ref "CO1") (pin "1") (pinfunction "1_1") (pintype "passive"))
      (node (ref "CO2") (pin "1") (pinfunction "1_1") (pintype "passive"))
      (node (ref "CO3") (pin "1") (pinfunction "1_1") (pintype "passive"))
      (node (ref "CSYNC2") (pin "1") (pinfunction "1_1") (pintype "passive"))
      (node (ref "JP1") (pin "1") (pinfunction "1_1") (pintype "passive"))
      (node (ref "L1") (pin "1") (pinfunction "P$1_1") (pintype "bidirectional"))
      (node (ref "R_SENSE1") (pin "1") (pinfunction "1_1") (pintype "passive"))
      (node (ref "R_SET1") (pin "2") (pinfunction "2_2") (pintype "passive"))
      (node (ref "U$5") (pin "P29") (pinfunction "VCC_P29") (pintype "bidirectional"))
    )
    (net (code "23") (name "3.3V_EN") (class "Default")
      (node (ref "D3") (pin "A") (pinfunction "A_A") (pintype "passive"))
      (node (ref "J2") (pin "3") (pinfunction "3_3") (pintype "passive"))
      (node (ref "R2") (pin "2") (pinfunction "2_2") (pintype "passive"))
      (node (ref "U$15") (pin "P4.0_GPIO") (pinfunction "P4.0_GPIO_P4.0_GPIO") (pintype "bidirectional"))
      (node (ref "U$6") (pin "P33") (pinfunction "EN_P33") (pintype "bidirectional"))
    )
    (net (code "24") (name "3.3V_IMON") (class "Default")
      (node (ref "R_AN7") (pin "2") (pinfunction "2_2") (pintype "passive"))
      (node (ref "R_IMON2") (pin "2") (pinfunction "2_2") (pintype "passive"))
      (node (ref "U$6") (pin "P2") (pinfunction "IMON_P2") (pintype "bidirectional"))
    )
    (net (code "25") (name "3.3V_VOUT") (class "Default")
      (node (ref "C_OUT1") (pin "1") (pinfunction "1_1") (pintype "passive"))
      (node (ref "U$2") (pin "P$54") (pinfunction "3.3V_P$54") (pintype "bidirectional"))
      (node (ref "U$2") (pin "P$55") (pinfunction "3.3V_P$55") (pintype "bidirectional"))
      (node (ref "U$5") (pin "P10") (pinfunction "OUT10_P10") (pintype "bidirectional"))
      (node (ref "U$5") (pin "P11") (pinfunction "OUT11_P11") (pintype "bidirectional"))
      (node (ref "U$5") (pin "P12") (pinfunction "OUT12_P12") (pintype "bidirectional"))
      (node (ref "U$5") (pin "P13") (pinfunction "OUT13_P13") (pintype "bidirectional"))
      (node (ref "U$5") (pin "P19") (pinfunction "OUT19_P19") (pintype "bidirectional"))
      (node (ref "U$5") (pin "P20") (pinfunction "OUT20_P20") (pintype "bidirectional"))
      (node (ref "U$5") (pin "P21") (pinfunction "OUT21_P21") (pintype "bidirectional"))
      (node (ref "U$5") (pin "P22") (pinfunction "OUT22_P22") (pintype "bidirectional"))
      (node (ref "U$5") (pin "P23") (pinfunction "OUT23_P23") (pintype "bidirectional"))
      (node (ref "U$5") (pin "P24") (pinfunction "OUT24_P24") (pintype "bidirectional"))
      (node (ref "U$5") (pin "P6") (pinfunction "OUT6_P6") (pintype "bidirectional"))
      (node (ref "U$5") (pin "P7") (pinfunction "OUT7_P7") (pintype "bidirectional"))
      (node (ref "U$5") (pin "P8") (pinfunction "OUT8_P8") (pintype "bidirectional"))
      (node (ref "U$5") (pin "P9") (pinfunction "OUT9_P9") (pintype "bidirectional"))
    )
    (net (code "26") (name "5VBUCK_EN") (class "Default")
      (node (ref "CEN2") (pin "1") (pinfunction "1_1") (pintype "passive"))
      (node (ref "J3") (pin "5") (pinfunction "5_5") (pintype "passive"))
      (node (ref "U$13") (pin "P$3") (pinfunction "RUN_P$3") (pintype "bidirectional"))
      (node (ref "U$15") (pin "P1.7_GPIO/PWM") (pinfunction "P1.7_GPIO/PWM_P1.7_GPIO/PWM") (pintype "bidirectional"))
    )
    (net (code "27") (name "5VBUCK_OUT") (class "Default")
      (node (ref "C2") (pin "1") (pinfunction "1_1") (pintype "passive"))
      (node (ref "C21") (pin "1") (pinfunction "1_1") (pintype "passive"))
      (node (ref "CO4") (pin "1") (pinfunction "1_1") (pintype "passive"))
      (node (ref "CO5") (pin "1") (pinfunction "1_1") (pintype "passive"))
      (node (ref "CO6") (pin "1") (pinfunction "1_1") (pintype "passive"))
      (node (ref "CSYNC4") (pin "1") (pinfunction "1_1") (pintype "passive"))
      (node (ref "JP2") (pin "1") (pinfunction "1_1") (pintype "passive"))
      (node (ref "L2") (pin "1") (pinfunction "P$1_1") (pintype "bidirectional"))
      (node (ref "R_SENSE2") (pin "1") (pinfunction "1_1") (pintype "passive"))
      (node (ref "R_SET2") (pin "2") (pinfunction "2_2") (pintype "passive"))
      (node (ref "U$6") (pin "P29") (pinfunction "VCC_P29") (pintype "bidirectional"))
    )
    (net (code "28") (name "5V_EN") (class "Default")
      (node (ref "D2") (pin "A") (pinfunction "A_A") (pintype "passive"))
      (node (ref "J2") (pin "2") (pinfunction "2_2") (pintype "passive"))
      (node (ref "R1") (pin "2") (pinfunction "2_2") (pintype "passive"))
      (node (ref "U$15") (pin "P7.4_GPIO") (pinfunction "P7.4_GPIO_P7.4_GPIO") (pintype "bidirectional"))
      (node (ref "U$5") (pin "P33") (pinfunction "EN_P33") (pintype "bidirectional"))
    )
    (net (code "29") (name "5V_IMON") (class "Default")
      (node (ref "R_AN8") (pin "2") (pinfunction "2_2") (pintype "passive"))
      (node (ref "R_IMON1") (pin "2") (pinfunction "2_2") (pintype "passive"))
      (node (ref "U$5") (pin "P2") (pinfunction "IMON_P2") (pintype "bidirectional"))
    )
    (net (code "30") (name "5V_VOUT") (class "Default")
      (node (ref "C_OUT2") (pin "1") (pinfunction "1_1") (pintype "passive"))
      (node (ref "U$2") (pin "P$50") (pinfunction "5V_P$50") (pintype "bidirectional"))
      (node (ref "U$2") (pin "P$51") (pinfunction "5V_P$51") (pintype "bidirectional"))
      (node (ref "U$6") (pin "P10") (pinfunction "OUT10_P10") (pintype "bidirectional"))
      (node (ref "U$6") (pin "P11") (pinfunction "OUT11_P11") (pintype "bidirectional"))
      (node (ref "U$6") (pin "P12") (pinfunction "OUT12_P12") (pintype "bidirectional"))
      (node (ref "U$6") (pin "P13") (pinfunction "OUT13_P13") (pintype "bidirectional"))
      (node (ref "U$6") (pin "P19") (pinfunction "OUT19_P19") (pintype "bidirectional"))
      (node (ref "U$6") (pin "P20") (pinfunction "OUT20_P20") (pintype "bidirectional"))
      (node (ref "U$6") (pin "P21") (pinfunction "OUT21_P21") (pintype "bidirectional"))
      (node (ref "U$6") (pin "P22") (pinfunction "OUT22_P22") (pintype "bidirectional"))
      (node (ref "U$6") (pin "P23") (pinfunction "OUT23_P23") (pintype "bidirectional"))
      (node (ref "U$6") (pin "P24") (pinfunction "OUT24_P24") (pintype "bidirectional"))
      (node (ref "U$6") (pin "P6") (pinfunction "OUT6_P6") (pintype "bidirectional"))
      (node (ref "U$6") (pin "P7") (pinfunction "OUT7_P7") (pintype "bidirectional"))
      (node (ref "U$6") (pin "P8") (pinfunction "OUT8_P8") (pintype "bidirectional"))
      (node (ref "U$6") (pin "P9") (pinfunction "OUT9_P9") (pintype "bidirectional"))
    )
    (net (code "31") (name "ADCS2_EN") (class "Default")
      (node (ref "D5") (pin "A") (pinfunction "A_A") (pintype "passive"))
      (node (ref "J3") (pin "1") (pinfunction "1_1") (pintype "passive"))
      (node (ref "R4") (pin "2") (pinfunction "2_2") (pintype "passive"))
      (node (ref "U$15") (pin "P4.3_GPIO") (pinfunction "P4.3_GPIO_P4.3_GPIO") (pintype "bidirectional"))
      (node (ref "U$8") (pin "P33") (pinfunction "EN_P33") (pintype "bidirectional"))
    )
    (net (code "32") (name "ADCS2_IMON") (class "Default")
      (node (ref "R_AN4") (pin "2") (pinfunction "2_2") (pintype "passive"))
      (node (ref "R_IMON4") (pin "2") (pinfunction "2_2") (pintype "passive"))
      (node (ref "U$8") (pin "P2") (pinfunction "IMON_P2") (pintype "bidirectional"))
    )
    (net (code "33") (name "COM1_EN") (class "Default")
      (node (ref "D9") (pin "A") (pinfunction "A_A") (pintype "passive"))
      (node (ref "J3") (pin "3") (pinfunction "3_3") (pintype "passive"))
      (node (ref "R8") (pin "2") (pinfunction "2_2") (pintype "passive"))
      (node (ref "U$12") (pin "P33") (pinfunction "EN_P33") (pintype "bidirectional"))
      (node (ref "U$15") (pin "P3.6_GPIO/PWM") (pinfunction "P3.6_GPIO/PWM_P3.6_GPIO/PWM") (pintype "bidirectional"))
    )
    (net (code "34") (name "COM1_IMON") (class "Default")
      (node (ref "R_AN2") (pin "2") (pinfunction "2_2") (pintype "passive"))
      (node (ref "R_IMON8") (pin "2") (pinfunction "2_2") (pintype "passive"))
      (node (ref "U$12") (pin "P2") (pinfunction "IMON_P2") (pintype "bidirectional"))
    )
    (net (code "35") (name "COM1_VOUT") (class "Default")
      (node (ref "C_OUT8") (pin "1") (pinfunction "1_1") (pintype "passive"))
      (node (ref "U$12") (pin "P10") (pinfunction "OUT10_P10") (pintype "bidirectional"))
      (node (ref "U$12") (pin "P11") (pinfunction "OUT11_P11") (pintype "bidirectional"))
      (node (ref "U$12") (pin "P12") (pinfunction "OUT12_P12") (pintype "bidirectional"))
      (node (ref "U$12") (pin "P13") (pinfunction "OUT13_P13") (pintype "bidirectional"))
      (node (ref "U$12") (pin "P19") (pinfunction "OUT19_P19") (pintype "bidirectional"))
      (node (ref "U$12") (pin "P20") (pinfunction "OUT20_P20") (pintype "bidirectional"))
      (node (ref "U$12") (pin "P21") (pinfunction "OUT21_P21") (pintype "bidirectional"))
      (node (ref "U$12") (pin "P22") (pinfunction "OUT22_P22") (pintype "bidirectional"))
      (node (ref "U$12") (pin "P23") (pinfunction "OUT23_P23") (pintype "bidirectional"))
      (node (ref "U$12") (pin "P24") (pinfunction "OUT24_P24") (pintype "bidirectional"))
      (node (ref "U$12") (pin "P6") (pinfunction "OUT6_P6") (pintype "bidirectional"))
      (node (ref "U$12") (pin "P7") (pinfunction "OUT7_P7") (pintype "bidirectional"))
      (node (ref "U$12") (pin "P8") (pinfunction "OUT8_P8") (pintype "bidirectional"))
      (node (ref "U$12") (pin "P9") (pinfunction "OUT9_P9") (pintype "bidirectional"))
      (node (ref "U$2") (pin "P$101") (pinfunction "COM1_VBAT_P$101") (pintype "bidirectional"))
      (node (ref "U$2") (pin "P$103") (pinfunction "COM1_VBAT_P$103") (pintype "bidirectional"))
    )
    (net (code "36") (name "COM2_EN") (class "Default")
      (node (ref "D8") (pin "A") (pinfunction "A_A") (pintype "passive"))
      (node (ref "J3") (pin "2") (pinfunction "2_2") (pintype "passive"))
      (node (ref "R7") (pin "2") (pinfunction "2_2") (pintype "passive"))
      (node (ref "U$11") (pin "P33") (pinfunction "EN_P33") (pintype "bidirectional"))
      (node (ref "U$15") (pin "P2.5_GPIO") (pinfunction "P2.5_GPIO_P2.5_GPIO") (pintype "bidirectional"))
    )
    (net (code "37") (name "COM2_IMON") (class "Default")
      (node (ref "R_AN3") (pin "2") (pinfunction "2_2") (pintype "passive"))
      (node (ref "R_IMON7") (pin "2") (pinfunction "2_2") (pintype "passive"))
      (node (ref "U$11") (pin "P2") (pinfunction "IMON_P2") (pintype "bidirectional"))
    )
    (net (code "38") (name "COM2_VOUT") (class "Default")
      (node (ref "C_OUT7") (pin "1") (pinfunction "1_1") (pintype "passive"))
      (node (ref "U$11") (pin "P10") (pinfunction "OUT10_P10") (pintype "bidirectional"))
      (node (ref "U$11") (pin "P11") (pinfunction "OUT11_P11") (pintype "bidirectional"))
      (node (ref "U$11") (pin "P12") (pinfunction "OUT12_P12") (pintype "bidirectional"))
      (node (ref "U$11") (pin "P13") (pinfunction "OUT13_P13") (pintype "bidirectional"))
      (node (ref "U$11") (pin "P19") (pinfunction "OUT19_P19") (pintype "bidirectional"))
      (node (ref "U$11") (pin "P20") (pinfunction "OUT20_P20") (pintype "bidirectional"))
      (node (ref "U$11") (pin "P21") (pinfunction "OUT21_P21") (pintype "bidirectional"))
      (node (ref "U$11") (pin "P22") (pinfunction "OUT22_P22") (pintype "bidirectional"))
      (node (ref "U$11") (pin "P23") (pinfunction "OUT23_P23") (pintype "bidirectional"))
      (node (ref "U$11") (pin "P24") (pinfunction "OUT24_P24") (pintype "bidirectional"))
      (node (ref "U$11") (pin "P6") (pinfunction "OUT6_P6") (pintype "bidirectional"))
      (node (ref "U$11") (pin "P7") (pinfunction "OUT7_P7") (pintype "bidirectional"))
      (node (ref "U$11") (pin "P8") (pinfunction "OUT8_P8") (pintype "bidirectional"))
      (node (ref "U$11") (pin "P9") (pinfunction "OUT9_P9") (pintype "bidirectional"))
      (node (ref "U$2") (pin "P$94") (pinfunction "RAHS_GND_P$94") (pintype "bidirectional"))
      (node (ref "U$2") (pin "P$97") (pinfunction "COM2_VBAT_P$97") (pintype "bidirectional"))
      (node (ref "U$2") (pin "P$99") (pinfunction "COM2_VBAT_P$99") (pintype "bidirectional"))
    )
    (net (code "39") (name "DEPLOYMENT_EN") (class "Default")
      (node (ref "D6") (pin "A") (pinfunction "A_A") (pintype "passive"))
      (node (ref "J3") (pin "4") (pinfunction "4_4") (pintype "passive"))
      (node (ref "R5") (pin "2") (pinfunction "2_2") (pintype "passive"))
      (node (ref "U$15") (pin "P3.7_GPIO/PWM") (pinfunction "P3.7_GPIO/PWM_P3.7_GPIO/PWM") (pintype "bidirectional"))
      (node (ref "U$9") (pin "P33") (pinfunction "EN_P33") (pintype "bidirectional"))
    )
    (net (code "40") (name "DEPLOYMENT_IMON") (class "Default")
      (node (ref "R_AN1") (pin "2") (pinfunction "2_2") (pintype "passive"))
      (node (ref "R_IMON5") (pin "2") (pinfunction "2_2") (pintype "passive"))
      (node (ref "U$9") (pin "P2") (pinfunction "IMON_P2") (pintype "bidirectional"))
    )
    (net (code "41") (name "DEPLOYMENT_VOUT") (class "Default")
      (node (ref "C_OUT5") (pin "1") (pinfunction "1_1") (pintype "passive"))
      (node (ref "J1") (pin "1") (pinfunction "1_1") (pintype "passive"))
      (node (ref "U$9") (pin "P10") (pinfunction "OUT10_P10") (pintype "bidirectional"))
      (node (ref "U$9") (pin "P11") (pinfunction "OUT11_P11") (pintype "bidirectional"))
      (node (ref "U$9") (pin "P12") (pinfunction "OUT12_P12") (pintype "bidirectional"))
      (node (ref "U$9") (pin "P13") (pinfunction "OUT13_P13") (pintype "bidirectional"))
      (node (ref "U$9") (pin "P19") (pinfunction "OUT19_P19") (pintype "bidirectional"))
      (node (ref "U$9") (pin "P20") (pinfunction "OUT20_P20") (pintype "bidirectional"))
      (node (ref "U$9") (pin "P21") (pinfunction "OUT21_P21") (pintype "bidirectional"))
      (node (ref "U$9") (pin "P22") (pinfunction "OUT22_P22") (pintype "bidirectional"))
      (node (ref "U$9") (pin "P23") (pinfunction "OUT23_P23") (pintype "bidirectional"))
      (node (ref "U$9") (pin "P24") (pinfunction "OUT24_P24") (pintype "bidirectional"))
      (node (ref "U$9") (pin "P6") (pinfunction "OUT6_P6") (pintype "bidirectional"))
      (node (ref "U$9") (pin "P7") (pinfunction "OUT7_P7") (pintype "bidirectional"))
      (node (ref "U$9") (pin "P8") (pinfunction "OUT8_P8") (pintype "bidirectional"))
      (node (ref "U$9") (pin "P9") (pinfunction "OUT9_P9") (pintype "bidirectional"))
    )
    (net (code "42") (name "ESTIMAT_EN") (class "Default")
      (node (ref "D4") (pin "A") (pinfunction "A_A") (pintype "passive"))
      (node (ref "J2") (pin "4") (pinfunction "4_4") (pintype "passive"))
      (node (ref "R3") (pin "2") (pinfunction "2_2") (pintype "passive"))
      (node (ref "U$15") (pin "P4.1_GPIO") (pinfunction "P4.1_GPIO_P4.1_GPIO") (pintype "bidirectional"))
      (node (ref "U$7") (pin "P33") (pinfunction "EN_P33") (pintype "bidirectional"))
    )
    (net (code "43") (name "ESTIMAT_IMON") (class "Default")
      (node (ref "R_AN6") (pin "2") (pinfunction "2_2") (pintype "passive"))
      (node (ref "R_IMON3") (pin "2") (pinfunction "2_2") (pintype "passive"))
      (node (ref "U$7") (pin "P2") (pinfunction "IMON_P2") (pintype "bidirectional"))
    )
    (net (code "44") (name "ESTIMAT_VOUT") (class "Default")
      (node (ref "C_OUT3") (pin "1") (pinfunction "1_1") (pintype "passive"))
      (node (ref "U$2") (pin "P$77") (pinfunction "ESTIMAT_VBAT_P$77") (pintype "bidirectional"))
      (node (ref "U$2") (pin "P$79") (pinfunction "ESTIMAT_VBAT_P$79") (pintype "bidirectional"))
      (node (ref "U$7") (pin "P10") (pinfunction "OUT10_P10") (pintype "bidirectional"))
      (node (ref "U$7") (pin "P11") (pinfunction "OUT11_P11") (pintype "bidirectional"))
      (node (ref "U$7") (pin "P12") (pinfunction "OUT12_P12") (pintype "bidirectional"))
      (node (ref "U$7") (pin "P13") (pinfunction "OUT13_P13") (pintype "bidirectional"))
      (node (ref "U$7") (pin "P19") (pinfunction "OUT19_P19") (pintype "bidirectional"))
      (node (ref "U$7") (pin "P20") (pinfunction "OUT20_P20") (pintype "bidirectional"))
      (node (ref "U$7") (pin "P21") (pinfunction "OUT21_P21") (pintype "bidirectional"))
      (node (ref "U$7") (pin "P22") (pinfunction "OUT22_P22") (pintype "bidirectional"))
      (node (ref "U$7") (pin "P23") (pinfunction "OUT23_P23") (pintype "bidirectional"))
      (node (ref "U$7") (pin "P24") (pinfunction "OUT24_P24") (pintype "bidirectional"))
      (node (ref "U$7") (pin "P6") (pinfunction "OUT6_P6") (pintype "bidirectional"))
      (node (ref "U$7") (pin "P7") (pinfunction "OUT7_P7") (pintype "bidirectional"))
      (node (ref "U$7") (pin "P8") (pinfunction "OUT8_P8") (pintype "bidirectional"))
      (node (ref "U$7") (pin "P9") (pinfunction "OUT9_P9") (pintype "bidirectional"))
    )
    (net (code "45") (name "GND") (class "Default")
      (node (ref "C1") (pin "2") (pinfunction "2_2") (pintype "passive"))
      (node (ref "C10") (pin "2") (pinfunction "2_2") (pintype "passive"))
      (node (ref "C11") (pin "2") (pinfunction "2_2") (pintype "passive"))
      (node (ref "C12") (pin "2") (pinfunction "2_2") (pintype "passive"))
      (node (ref "C13") (pin "2") (pinfunction "2_2") (pintype "passive"))
      (node (ref "C2") (pin "2") (pinfunction "2_2") (pintype "passive"))
      (node (ref "C3") (pin "2") (pinfunction "2_2") (pintype "passive"))
      (node (ref "C4") (pin "2") (pinfunction "2_2") (pintype "passive"))
      (node (ref "C5") (pin "2") (pinfunction "2_2") (pintype "passive"))
      (node (ref "C6") (pin "2") (pinfunction "2_2") (pintype "passive"))
      (node (ref "C7") (pin "2") (pinfunction "2_2") (pintype "passive"))
      (node (ref "C8") (pin "2") (pinfunction "2_2") (pintype "passive"))
      (node (ref "C9") (pin "2") (pinfunction "2_2") (pintype "passive"))
      (node (ref "CA1") (pin "2") (pinfunction "2_2") (pintype "passive"))
      (node (ref "CA10") (pin "2") (pinfunction "2_2") (pintype "passive"))
      (node (ref "CA11") (pin "2") (pinfunction "2_2") (pintype "passive"))
      (node (ref "CA2") (pin "2") (pinfunction "2_2") (pintype "passive"))
      (node (ref "CA3") (pin "2") (pinfunction "2_2") (pintype "passive"))
      (node (ref "CA4") (pin "2") (pinfunction "2_2") (pintype "passive"))
      (node (ref "CA5") (pin "2") (pinfunction "2_2") (pintype "passive"))
      (node (ref "CA6") (pin "2") (pinfunction "2_2") (pintype "passive"))
      (node (ref "CA7") (pin "2") (pinfunction "2_2") (pintype "passive"))
      (node (ref "CA8") (pin "2") (pinfunction "2_2") (pintype "passive"))
      (node (ref "CA9") (pin "2") (pinfunction "2_2") (pintype "passive"))
      (node (ref "CEN1") (pin "2") (pinfunction "2_2") (pintype "passive"))
      (node (ref "CEN2") (pin "2") (pinfunction "2_2") (pintype "passive"))
      (node (ref "CIN2") (pin "2") (pinfunction "2_2") (pintype "passive"))
      (node (ref "CIN3") (pin "2") (pinfunction "2_2") (pintype "passive"))
      (node (ref "CIN4") (pin "2") (pinfunction "2_2") (pintype "passive"))
      (node (ref "CIN5") (pin "2") (pinfunction "2_2") (pintype "passive"))
      (node (ref "CINTV1") (pin "2") (pinfunction "2_2") (pintype "passive"))
      (node (ref "CINTV2") (pin "2") (pinfunction "2_2") (pintype "passive"))
      (node (ref "CO1") (pin "2") (pinfunction "2_2") (pintype "passive"))
      (node (ref "CO2") (pin "2") (pinfunction "2_2") (pintype "passive"))
      (node (ref "CO3") (pin "2") (pinfunction "2_2") (pintype "passive"))
      (node (ref "CO4") (pin "2") (pinfunction "2_2") (pintype "passive"))
      (node (ref "CO5") (pin "2") (pinfunction "2_2") (pintype "passive"))
      (node (ref "CO6") (pin "2") (pinfunction "2_2") (pintype "passive"))
      (node (ref "CSYNC3") (pin "2") (pinfunction "2_2") (pintype "passive"))
      (node (ref "CSYNC5") (pin "2") (pinfunction "2_2") (pintype "passive"))
      (node (ref "CV1") (pin "2") (pinfunction "2_2") (pintype "passive"))
      (node (ref "CV2") (pin "2") (pinfunction "2_2") (pintype "passive"))
      (node (ref "CV3") (pin "2") (pinfunction "2_2") (pintype "passive"))
      (node (ref "CV4") (pin "2") (pinfunction "2_2") (pintype "passive"))
      (node (ref "CV5") (pin "2") (pinfunction "2_2") (pintype "passive"))
      (node (ref "CV6") (pin "2") (pinfunction "2_2") (pintype "passive"))
      (node (ref "C_OUT") (pin "2") (pinfunction "2_2") (pintype "passive"))
      (node (ref "C_OUT1") (pin "2") (pinfunction "2_2") (pintype "passive"))
      (node (ref "C_OUT2") (pin "2") (pinfunction "2_2") (pintype "passive"))
      (node (ref "C_OUT3") (pin "2") (pinfunction "2_2") (pintype "passive"))
      (node (ref "C_OUT4") (pin "2") (pinfunction "2_2") (pintype "passive"))
      (node (ref "C_OUT5") (pin "2") (pinfunction "2_2") (pintype "passive"))
      (node (ref "C_OUT6") (pin "2") (pinfunction "2_2") (pintype "passive"))
      (node (ref "C_OUT7") (pin "2") (pinfunction "2_2") (pintype "passive"))
      (node (ref "C_OUT8") (pin "2") (pinfunction "2_2") (pintype "passive"))
      (node (ref "C_TIMER") (pin "2") (pinfunction "2_2") (pintype "passive"))
      (node (ref "C_TIMER1") (pin "2") (pinfunction "2_2") (pintype "passive"))
      (node (ref "C_TIMER2") (pin "2") (pinfunction "2_2") (pintype "passive"))
      (node (ref "C_TIMER3") (pin "2") (pinfunction "2_2") (pintype "passive"))
      (node (ref "C_TIMER4") (pin "2") (pinfunction "2_2") (pintype "passive"))
      (node (ref "C_TIMER5") (pin "2") (pinfunction "2_2") (pintype "passive"))
      (node (ref "C_TIMER6") (pin "2") (pinfunction "2_2") (pintype "passive"))
      (node (ref "C_TIMER7") (pin "2") (pinfunction "2_2") (pintype "passive"))
      (node (ref "C_TIMER8") (pin "2") (pinfunction "2_2") (pintype "passive"))
      (node (ref "IC1") (pin "2") (pinfunction "GND_2") (pintype "power_in"))
      (node (ref "IC2") (pin "2") (pinfunction "GND_2") (pintype "power_in"))
      (node (ref "J1") (pin "2") (pinfunction "2_2") (pintype "passive"))
      (node (ref "R1") (pin "1") (pinfunction "1_1") (pintype "passive"))
      (node (ref "R10") (pin "1") (pinfunction "1_1") (pintype "passive"))
      (node (ref "R13") (pin "1") (pinfunction "1_1") (pintype "passive"))
      (node (ref "R2") (pin "1") (pinfunction "1_1") (pintype "passive"))
      (node (ref "R3") (pin "1") (pinfunction "1_1") (pintype "passive"))
      (node (ref "R4") (pin "1") (pinfunction "1_1") (pintype "passive"))
      (node (ref "R5") (pin "1") (pinfunction "1_1") (pintype "passive"))
      (node (ref "R6") (pin "1") (pinfunction "1_1") (pintype "passive"))
      (node (ref "R7") (pin "1") (pinfunction "1_1") (pintype "passive"))
      (node (ref "R8") (pin "1") (pinfunction "1_1") (pintype "passive"))
      (node (ref "R9") (pin "1") (pinfunction "1_1") (pintype "passive"))
      (node (ref "RSYNC1") (pin "2") (pinfunction "2_2") (pintype "passive"))
      (node (ref "RSYNC2") (pin "2") (pinfunction "2_2") (pintype "passive"))
      (node (ref "R_3.3V") (pin "1") (pinfunction "1_1") (pintype "passive"))
      (node (ref "R_5V") (pin "1") (pinfunction "1_1") (pintype "passive"))
      (node (ref "R_ADCS2") (pin "1") (pinfunction "1_1") (pintype "passive"))
      (node (ref "R_BOOT") (pin "1") (pinfunction "1_1") (pintype "passive"))
      (node (ref "R_COM1") (pin "1") (pinfunction "1_1") (pintype "passive"))
      (node (ref "R_COM2") (pin "1") (pinfunction "1_1") (pintype "passive"))
      (node (ref "R_EST") (pin "1") (pinfunction "1_1") (pintype "passive"))
      (node (ref "R_IMON") (pin "1") (pinfunction "1_1") (pintype "passive"))
      (node (ref "R_IMON1") (pin "1") (pinfunction "1_1") (pintype "passive"))
      (node (ref "R_IMON2") (pin "1") (pinfunction "1_1") (pintype "passive"))
      (node (ref "R_IMON3") (pin "1") (pinfunction "1_1") (pintype "passive"))
      (node (ref "R_IMON4") (pin "1") (pinfunction "1_1") (pintype "passive"))
      (node (ref "R_IMON5") (pin "1") (pinfunction "1_1") (pintype "passive"))
      (node (ref "R_IMON6") (pin "1") (pinfunction "1_1") (pintype "passive"))
      (node (ref "R_IMON7") (pin "1") (pinfunction "1_1") (pintype "passive"))
      (node (ref "R_IMON8") (pin "1") (pinfunction "1_1") (pintype "passive"))
      (node (ref "R_PPT") (pin "1") (pinfunction "1_1") (pintype "passive"))
      (node (ref "R_PROG") (pin "1") (pinfunction "1_1") (pintype "passive"))
      (node (ref "R_PROG1") (pin "1") (pinfunction "1_1") (pintype "passive"))
      (node (ref "R_PROG2") (pin "1") (pinfunction "1_1") (pintype "passive"))
      (node (ref "R_PROG3") (pin "1") (pinfunction "1_1") (pintype "passive"))
      (node (ref "R_PROG4") (pin "1") (pinfunction "1_1") (pintype "passive"))
      (node (ref "R_PROG5") (pin "1") (pinfunction "1_1") (pintype "passive"))
      (node (ref "R_PROG6") (pin "1") (pinfunction "1_1") (pintype "passive"))
      (node (ref "R_PROG7") (pin "1") (pinfunction "1_1") (pintype "passive"))
      (node (ref "R_PROG8") (pin "1") (pinfunction "1_1") (pintype "passive"))
      (node (ref "R_RAHS") (pin "1") (pinfunction "1_1") (pintype "passive"))
      (node (ref "U$1") (pin "P$37") (pinfunction "GND37_P$37") (pintype "bidirectional"))
      (node (ref "U$1") (pin "P1") (pinfunction "OV_P1") (pintype "bidirectional"))
      (node (ref "U$1") (pin "P28") (pinfunction "GND28_P28") (pintype "bidirectional"))
      (node (ref "U$1") (pin "P32") (pinfunction "GND32_P32") (pintype "bidirectional"))
      (node (ref "U$1") (pin "P36") (pinfunction "GND36_P36") (pintype "bidirectional"))
      (node (ref "U$1") (pin "P4") (pinfunction "GND4_P4") (pintype "bidirectional"))
      (node (ref "U$10") (pin "P$37") (pinfunction "GND37_P$37") (pintype "bidirectional"))
      (node (ref "U$10") (pin "P1") (pinfunction "OV_P1") (pintype "bidirectional"))
      (node (ref "U$10") (pin "P28") (pinfunction "GND28_P28") (pintype "bidirectional"))
      (node (ref "U$10") (pin "P32") (pinfunction "GND32_P32") (pintype "bidirectional"))
      (node (ref "U$10") (pin "P36") (pinfunction "GND36_P36") (pintype "bidirectional"))
      (node (ref "U$10") (pin "P4") (pinfunction "GND4_P4") (pintype "bidirectional"))
      (node (ref "U$11") (pin "P$37") (pinfunction "GND37_P$37") (pintype "bidirectional"))
      (node (ref "U$11") (pin "P1") (pinfunction "OV_P1") (pintype "bidirectional"))
      (node (ref "U$11") (pin "P28") (pinfunction "GND28_P28") (pintype "bidirectional"))
      (node (ref "U$11") (pin "P32") (pinfunction "GND32_P32") (pintype "bidirectional"))
      (node (ref "U$11") (pin "P36") (pinfunction "GND36_P36") (pintype "bidirectional"))
      (node (ref "U$11") (pin "P4") (pinfunction "GND4_P4") (pintype "bidirectional"))
      (node (ref "U$12") (pin "P$37") (pinfunction "GND37_P$37") (pintype "bidirectional"))
      (node (ref "U$12") (pin "P1") (pinfunction "OV_P1") (pintype "bidirectional"))
      (node (ref "U$12") (pin "P28") (pinfunction "GND28_P28") (pintype "bidirectional"))
      (node (ref "U$12") (pin "P32") (pinfunction "GND32_P32") (pintype "bidirectional"))
      (node (ref "U$12") (pin "P36") (pinfunction "GND36_P36") (pintype "bidirectional"))
      (node (ref "U$12") (pin "P4") (pinfunction "GND4_P4") (pintype "bidirectional"))
      (node (ref "U$13") (pin "P$8") (pinfunction "GND_P$8") (pintype "bidirectional"))
      (node (ref "U$13") (pin "P$9") (pinfunction "GNDP_P$9") (pintype "bidirectional"))
      (node (ref "U$14") (pin "P$8") (pinfunction "GND_P$8") (pintype "bidirectional"))
      (node (ref "U$14") (pin "P$9") (pinfunction "GNDP_P$9") (pintype "bidirectional"))
      (node (ref "U$15") (pin "GND@1") (pinfunction "GND_GND@1") (pintype "bidirectional"))
      (node (ref "U$15") (pin "GND@10") (pinfunction "GND_GND@10") (pintype "bidirectional"))
      (node (ref "U$15") (pin "GND@11") (pinfunction "GND_GND@11") (pintype "bidirectional"))
      (node (ref "U$15") (pin "GND@12") (pinfunction "GND_GND@12") (pintype "bidirectional"))
      (node (ref "U$15") (pin "GND@13") (pinfunction "GND_GND@13") (pintype "bidirectional"))
      (node (ref "U$15") (pin "GND@14") (pinfunction "GND_GND@14") (pintype "bidirectional"))
      (node (ref "U$15") (pin "GND@15") (pinfunction "GND_GND@15") (pintype "bidirectional"))
      (node (ref "U$15") (pin "GND@16") (pinfunction "GND_GND@16") (pintype "bidirectional"))
      (node (ref "U$15") (pin "GND@17") (pinfunction "GND_GND@17") (pintype "bidirectional"))
      (node (ref "U$15") (pin "GND@2") (pinfunction "GND_GND@2") (pintype "bidirectional"))
      (node (ref "U$15") (pin "GND@26") (pinfunction "GND_GND@26") (pintype "bidirectional"))
      (node (ref "U$15") (pin "GND@3") (pinfunction "GND_GND@3") (pintype "bidirectional"))
      (node (ref "U$15") (pin "GND@4") (pinfunction "GND_GND@4") (pintype "bidirectional"))
      (node (ref "U$15") (pin "GND@5") (pinfunction "GND_GND@5") (pintype "bidirectional"))
      (node (ref "U$15") (pin "GND@7") (pinfunction "GND_GND@7") (pintype "bidirectional"))
      (node (ref "U$15") (pin "GND@8") (pinfunction "GND_GND@8") (pintype "bidirectional"))
      (node (ref "U$15") (pin "GND@9") (pinfunction "GND_GND@9") (pintype "bidirectional"))
      (node (ref "U$16") (pin "5") (pinfunction "GND_5") (pintype "bidirectional"))
      (node (ref "U$16") (pin "6") (pinfunction "GND_6") (pintype "bidirectional"))
      (node (ref "U$2") (pin "P$1") (pinfunction "PPT_GND_P$1") (pintype "bidirectional"))
      (node (ref "U$2") (pin "P$100") (pinfunction "COM2_GND_P$100") (pintype "bidirectional"))
      (node (ref "U$2") (pin "P$102") (pinfunction "COM1_GND_P$102") (pintype "bidirectional"))
      (node (ref "U$2") (pin "P$104") (pinfunction "COM1_GND_P$104") (pintype "bidirectional"))
      (node (ref "U$2") (pin "P$11") (pinfunction "PPT_GND_P$11") (pintype "bidirectional"))
      (node (ref "U$2") (pin "P$14") (pinfunction "PPT_GND_P$14") (pintype "bidirectional"))
      (node (ref "U$2") (pin "P$16") (pinfunction "PPT_GND_P$16") (pintype "bidirectional"))
      (node (ref "U$2") (pin "P$17") (pinfunction "DISTRI_GND_P$17") (pintype "bidirectional"))
      (node (ref "U$2") (pin "P$19") (pinfunction "DISTRI_GND_P$19") (pintype "bidirectional"))
      (node (ref "U$2") (pin "P$22") (pinfunction "DISTRI_GND_P$22") (pintype "bidirectional"))
      (node (ref "U$2") (pin "P$24") (pinfunction "DISTRI_GND_P$24") (pintype "bidirectional"))
      (node (ref "U$2") (pin "P$25") (pinfunction "DISTRI_GND_P$25") (pintype "bidirectional"))
      (node (ref "U$2") (pin "P$27") (pinfunction "DISTRI_GND_P$27") (pintype "bidirectional"))
      (node (ref "U$2") (pin "P$3") (pinfunction "PPT_GND_P$3") (pintype "bidirectional"))
      (node (ref "U$2") (pin "P$30") (pinfunction "DISTRI_GND_P$30") (pintype "bidirectional"))
      (node (ref "U$2") (pin "P$32") (pinfunction "DISTRI_GND_P$32") (pintype "bidirectional"))
      (node (ref "U$2") (pin "P$46") (pinfunction "MCU_GND_P$46") (pintype "bidirectional"))
      (node (ref "U$2") (pin "P$47") (pinfunction "MCU_GND_P$47") (pintype "bidirectional"))
      (node (ref "U$2") (pin "P$58") (pinfunction "MCU_GND_P$58") (pintype "bidirectional"))
      (node (ref "U$2") (pin "P$59") (pinfunction "MCU_GND_P$59") (pintype "bidirectional"))
      (node (ref "U$2") (pin "P$6") (pinfunction "PPT_GND_P$6") (pintype "bidirectional"))
      (node (ref "U$2") (pin "P$78") (pinfunction "ESTIMAT_GND_P$78") (pintype "bidirectional"))
      (node (ref "U$2") (pin "P$8") (pinfunction "PPT_GND_P$8") (pintype "bidirectional"))
      (node (ref "U$2") (pin "P$80") (pinfunction "ESTIMAT_GND_P$80") (pintype "bidirectional"))
      (node (ref "U$2") (pin "P$82") (pinfunction "ADCS2_GND_P$82") (pintype "bidirectional"))
      (node (ref "U$2") (pin "P$84") (pinfunction "ADCS2_GND_P$84") (pintype "bidirectional"))
      (node (ref "U$2") (pin "P$86") (pinfunction "BDOT_GND_P$86") (pintype "bidirectional"))
      (node (ref "U$2") (pin "P$88") (pinfunction "BDOT_GND_P$88") (pintype "bidirectional"))
      (node (ref "U$2") (pin "P$9") (pinfunction "PPT_GND_P$9") (pintype "bidirectional"))
      (node (ref "U$2") (pin "P$93") (pinfunction "RAHS_VBAT_P$93") (pintype "bidirectional"))
      (node (ref "U$2") (pin "P$98") (pinfunction "COM2_GND_P$98") (pintype "bidirectional"))
      (node (ref "U$5") (pin "P$37") (pinfunction "GND37_P$37") (pintype "bidirectional"))
      (node (ref "U$5") (pin "P1") (pinfunction "OV_P1") (pintype "bidirectional"))
      (node (ref "U$5") (pin "P28") (pinfunction "GND28_P28") (pintype "bidirectional"))
      (node (ref "U$5") (pin "P32") (pinfunction "GND32_P32") (pintype "bidirectional"))
      (node (ref "U$5") (pin "P36") (pinfunction "GND36_P36") (pintype "bidirectional"))
      (node (ref "U$5") (pin "P4") (pinfunction "GND4_P4") (pintype "bidirectional"))
      (node (ref "U$6") (pin "P$37") (pinfunction "GND37_P$37") (pintype "bidirectional"))
      (node (ref "U$6") (pin "P1") (pinfunction "OV_P1") (pintype "bidirectional"))
      (node (ref "U$6") (pin "P28") (pinfunction "GND28_P28") (pintype "bidirectional"))
      (node (ref "U$6") (pin "P32") (pinfunction "GND32_P32") (pintype "bidirectional"))
      (node (ref "U$6") (pin "P36") (pinfunction "GND36_P36") (pintype "bidirectional"))
      (node (ref "U$6") (pin "P4") (pinfunction "GND4_P4") (pintype "bidirectional"))
      (node (ref "U$7") (pin "P$37") (pinfunction "GND37_P$37") (pintype "bidirectional"))
      (node (ref "U$7") (pin "P1") (pinfunction "OV_P1") (pintype "bidirectional"))
      (node (ref "U$7") (pin "P28") (pinfunction "GND28_P28") (pintype "bidirectional"))
      (node (ref "U$7") (pin "P32") (pinfunction "GND32_P32") (pintype "bidirectional"))
      (node (ref "U$7") (pin "P36") (pinfunction "GND36_P36") (pintype "bidirectional"))
      (node (ref "U$7") (pin "P4") (pinfunction "GND4_P4") (pintype "bidirectional"))
      (node (ref "U$8") (pin "P$37") (pinfunction "GND37_P$37") (pintype "bidirectional"))
      (node (ref "U$8") (pin "P1") (pinfunction "OV_P1") (pintype "bidirectional"))
      (node (ref "U$8") (pin "P28") (pinfunction "GND28_P28") (pintype "bidirectional"))
      (node (ref "U$8") (pin "P32") (pinfunction "GND32_P32") (pintype "bidirectional"))
      (node (ref "U$8") (pin "P36") (pinfunction "GND36_P36") (pintype "bidirectional"))
      (node (ref "U$8") (pin "P4") (pinfunction "GND4_P4") (pintype "bidirectional"))
      (node (ref "U$9") (pin "P$37") (pinfunction "GND37_P$37") (pintype "bidirectional"))
      (node (ref "U$9") (pin "P1") (pinfunction "OV_P1") (pintype "bidirectional"))
      (node (ref "U$9") (pin "P28") (pinfunction "GND28_P28") (pintype "bidirectional"))
      (node (ref "U$9") (pin "P32") (pinfunction "GND32_P32") (pintype "bidirectional"))
      (node (ref "U$9") (pin "P36") (pinfunction "GND36_P36") (pintype "bidirectional"))
      (node (ref "U$9") (pin "P4") (pinfunction "GND4_P4") (pintype "bidirectional"))
    )
    (net (code "46") (name "MAG_VOUT") (class "Default")
      (node (ref "C_OUT4") (pin "1") (pinfunction "1_1") (pintype "passive"))
      (node (ref "U$2") (pin "P$85") (pinfunction "BDOT_VBAT_P$85") (pintype "bidirectional"))
      (node (ref "U$2") (pin "P$87") (pinfunction "BDOT_VBAT_P$87") (pintype "bidirectional"))
      (node (ref "U$8") (pin "P10") (pinfunction "OUT10_P10") (pintype "bidirectional"))
      (node (ref "U$8") (pin "P11") (pinfunction "OUT11_P11") (pintype "bidirectional"))
      (node (ref "U$8") (pin "P12") (pinfunction "OUT12_P12") (pintype "bidirectional"))
      (node (ref "U$8") (pin "P13") (pinfunction "OUT13_P13") (pintype "bidirectional"))
      (node (ref "U$8") (pin "P19") (pinfunction "OUT19_P19") (pintype "bidirectional"))
      (node (ref "U$8") (pin "P20") (pinfunction "OUT20_P20") (pintype "bidirectional"))
      (node (ref "U$8") (pin "P21") (pinfunction "OUT21_P21") (pintype "bidirectional"))
      (node (ref "U$8") (pin "P22") (pinfunction "OUT22_P22") (pintype "bidirectional"))
      (node (ref "U$8") (pin "P23") (pinfunction "OUT23_P23") (pintype "bidirectional"))
      (node (ref "U$8") (pin "P24") (pinfunction "OUT24_P24") (pintype "bidirectional"))
      (node (ref "U$8") (pin "P6") (pinfunction "OUT6_P6") (pintype "bidirectional"))
      (node (ref "U$8") (pin "P7") (pinfunction "OUT7_P7") (pintype "bidirectional"))
      (node (ref "U$8") (pin "P8") (pinfunction "OUT8_P8") (pintype "bidirectional"))
      (node (ref "U$8") (pin "P9") (pinfunction "OUT9_P9") (pintype "bidirectional"))
    )
    (net (code "47") (name "Net-(D1-PadC)") (class "Default")
      (node (ref "D1") (pin "C") (pinfunction "C_C") (pintype "passive"))
      (node (ref "R_PPT") (pin "2") (pinfunction "2_2") (pintype "passive"))
    )
    (net (code "48") (name "Net-(D2-PadC)") (class "Default")
      (node (ref "D2") (pin "C") (pinfunction "C_C") (pintype "passive"))
      (node (ref "R_5V") (pin "2") (pinfunction "2_2") (pintype "passive"))
    )
    (net (code "49") (name "Net-(D3-PadC)") (class "Default")
      (node (ref "D3") (pin "C") (pinfunction "C_C") (pintype "passive"))
      (node (ref "R_3.3V") (pin "2") (pinfunction "2_2") (pintype "passive"))
    )
    (net (code "50") (name "Net-(D4-PadC)") (class "Default")
      (node (ref "D4") (pin "C") (pinfunction "C_C") (pintype "passive"))
      (node (ref "R_EST") (pin "2") (pinfunction "2_2") (pintype "passive"))
    )
    (net (code "51") (name "Net-(D5-PadC)") (class "Default")
      (node (ref "D5") (pin "C") (pinfunction "C_C") (pintype "passive"))
      (node (ref "R_ADCS2") (pin "2") (pinfunction "2_2") (pintype "passive"))
    )
    (net (code "52") (name "Net-(D6-PadC)") (class "Default")
      (node (ref "D6") (pin "C") (pinfunction "C_C") (pintype "passive"))
      (node (ref "R_BOOT") (pin "2") (pinfunction "2_2") (pintype "passive"))
    )
    (net (code "53") (name "Net-(D7-PadC)") (class "Default")
      (node (ref "D7") (pin "C") (pinfunction "C_C") (pintype "passive"))
      (node (ref "R_RAHS") (pin "2") (pinfunction "2_2") (pintype "passive"))
    )
    (net (code "54") (name "Net-(D8-PadC)") (class "Default")
      (node (ref "D8") (pin "C") (pinfunction "C_C") (pintype "passive"))
      (node (ref "R_COM2") (pin "2") (pinfunction "2_2") (pintype "passive"))
    )
    (net (code "55") (name "Net-(D9-PadC)") (class "Default")
      (node (ref "D9") (pin "C") (pinfunction "C_C") (pintype "passive"))
      (node (ref "R_COM1") (pin "2") (pinfunction "2_2") (pintype "passive"))
    )
    (net (code "56") (name "Net-(L1-P$2)") (class "Default")
      (node (ref "L1") (pin "2") (pinfunction "P$2_2") (pintype "bidirectional"))
      (node (ref "U$13") (pin "P$1") (pinfunction "SW_P$1") (pintype "bidirectional"))
    )
    (net (code "57") (name "Net-(L2-P$2)") (class "Default")
      (node (ref "L2") (pin "2") (pinfunction "P$2_2") (pintype "bidirectional"))
      (node (ref "U$14") (pin "P$1") (pinfunction "SW_P$1") (pintype "bidirectional"))
    )
    (net (code "58") (name "Net-(U$1-DRAIN14)") (class "Default")
      (node (ref "R_SENSE") (pin "2") (pinfunction "2_2") (pintype "passive"))
      (node (ref "U$1") (pin "P$38") (pinfunction "DRAIN38_P$38") (pintype "bidirectional"))
      (node (ref "U$1") (pin "P14") (pinfunction "DRAIN14_P14") (pintype "bidirectional"))
      (node (ref "U$1") (pin "P15") (pinfunction "DRAIN15_P15") (pintype "bidirectional"))
      (node (ref "U$1") (pin "P16") (pinfunction "DRAIN16_P16") (pintype "bidirectional"))
      (node (ref "U$1") (pin "P17") (pinfunction "DRAIN17_P17") (pintype "bidirectional"))
      (node (ref "U$1") (pin "P18") (pinfunction "DRAIN18_P18") (pintype "bidirectional"))
      (node (ref "U$1") (pin "P26") (pinfunction "SENSE_P26") (pintype "bidirectional"))
      (node (ref "U$1") (pin "P27") (pinfunction "DRAIN27_P27") (pintype "bidirectional"))
      (node (ref "U$1") (pin "P5") (pinfunction "DRAIN5_P5") (pintype "bidirectional"))
    )
    (net (code "59") (name "Net-(U$1-PROG)") (class "Default")
      (node (ref "R_PROG") (pin "2") (pinfunction "2_2") (pintype "passive"))
      (node (ref "U$1") (pin "P34") (pinfunction "PROG_P34") (pintype "bidirectional"))
    )
    (net (code "60") (name "Net-(U$1-SET)") (class "Default")
      (node (ref "R_SET") (pin "1") (pinfunction "1_1") (pintype "passive"))
      (node (ref "U$1") (pin "P3") (pinfunction "SET_P3") (pintype "bidirectional"))
    )
    (net (code "61") (name "Net-(U$1-TIMER)") (class "Default")
      (node (ref "C_TIMER") (pin "1") (pinfunction "1_1") (pintype "passive"))
      (node (ref "U$1") (pin "P35") (pinfunction "TIMER_P35") (pintype "bidirectional"))
    )
    (net (code "62") (name "Net-(U$5-DRAIN14)") (class "Default")
      (node (ref "R_SENSE1") (pin "2") (pinfunction "2_2") (pintype "passive"))
      (node (ref "U$5") (pin "P$38") (pinfunction "DRAIN38_P$38") (pintype "bidirectional"))
      (node (ref "U$5") (pin "P14") (pinfunction "DRAIN14_P14") (pintype "bidirectional"))
      (node (ref "U$5") (pin "P15") (pinfunction "DRAIN15_P15") (pintype "bidirectional"))
      (node (ref "U$5") (pin "P16") (pinfunction "DRAIN16_P16") (pintype "bidirectional"))
      (node (ref "U$5") (pin "P17") (pinfunction "DRAIN17_P17") (pintype "bidirectional"))
      (node (ref "U$5") (pin "P18") (pinfunction "DRAIN18_P18") (pintype "bidirectional"))
      (node (ref "U$5") (pin "P26") (pinfunction "SENSE_P26") (pintype "bidirectional"))
      (node (ref "U$5") (pin "P27") (pinfunction "DRAIN27_P27") (pintype "bidirectional"))
      (node (ref "U$5") (pin "P5") (pinfunction "DRAIN5_P5") (pintype "bidirectional"))
    )
    (net (code "63") (name "Net-(U$5-PROG)") (class "Default")
      (node (ref "R_PROG1") (pin "2") (pinfunction "2_2") (pintype "passive"))
      (node (ref "U$5") (pin "P34") (pinfunction "PROG_P34") (pintype "bidirectional"))
    )
    (net (code "64") (name "Net-(U$5-SET)") (class "Default")
      (node (ref "R_SET1") (pin "1") (pinfunction "1_1") (pintype "passive"))
      (node (ref "U$5") (pin "P3") (pinfunction "SET_P3") (pintype "bidirectional"))
    )
    (net (code "65") (name "Net-(U$5-TIMER)") (class "Default")
      (node (ref "C_TIMER1") (pin "1") (pinfunction "1_1") (pintype "passive"))
      (node (ref "U$5") (pin "P35") (pinfunction "TIMER_P35") (pintype "bidirectional"))
    )
    (net (code "66") (name "Net-(U$6-DRAIN14)") (class "Default")
      (node (ref "R_SENSE2") (pin "2") (pinfunction "2_2") (pintype "passive"))
      (node (ref "U$6") (pin "P$38") (pinfunction "DRAIN38_P$38") (pintype "bidirectional"))
      (node (ref "U$6") (pin "P14") (pinfunction "DRAIN14_P14") (pintype "bidirectional"))
      (node (ref "U$6") (pin "P15") (pinfunction "DRAIN15_P15") (pintype "bidirectional"))
      (node (ref "U$6") (pin "P16") (pinfunction "DRAIN16_P16") (pintype "bidirectional"))
      (node (ref "U$6") (pin "P17") (pinfunction "DRAIN17_P17") (pintype "bidirectional"))
      (node (ref "U$6") (pin "P18") (pinfunction "DRAIN18_P18") (pintype "bidirectional"))
      (node (ref "U$6") (pin "P26") (pinfunction "SENSE_P26") (pintype "bidirectional"))
      (node (ref "U$6") (pin "P27") (pinfunction "DRAIN27_P27") (pintype "bidirectional"))
      (node (ref "U$6") (pin "P5") (pinfunction "DRAIN5_P5") (pintype "bidirectional"))
    )
    (net (code "67") (name "Net-(U$6-PROG)") (class "Default")
      (node (ref "R_PROG2") (pin "2") (pinfunction "2_2") (pintype "passive"))
      (node (ref "U$6") (pin "P34") (pinfunction "PROG_P34") (pintype "bidirectional"))
    )
    (net (code "68") (name "Net-(U$6-SET)") (class "Default")
      (node (ref "R_SET2") (pin "1") (pinfunction "1_1") (pintype "passive"))
      (node (ref "U$6") (pin "P3") (pinfunction "SET_P3") (pintype "bidirectional"))
    )
    (net (code "69") (name "Net-(U$6-TIMER)") (class "Default")
      (node (ref "C_TIMER2") (pin "1") (pinfunction "1_1") (pintype "passive"))
      (node (ref "U$6") (pin "P35") (pinfunction "TIMER_P35") (pintype "bidirectional"))
    )
    (net (code "70") (name "Net-(U$7-DRAIN14)") (class "Default")
      (node (ref "R_SENSE3") (pin "2") (pinfunction "2_2") (pintype "passive"))
      (node (ref "U$7") (pin "P$38") (pinfunction "DRAIN38_P$38") (pintype "bidirectional"))
      (node (ref "U$7") (pin "P14") (pinfunction "DRAIN14_P14") (pintype "bidirectional"))
      (node (ref "U$7") (pin "P15") (pinfunction "DRAIN15_P15") (pintype "bidirectional"))
      (node (ref "U$7") (pin "P16") (pinfunction "DRAIN16_P16") (pintype "bidirectional"))
      (node (ref "U$7") (pin "P17") (pinfunction "DRAIN17_P17") (pintype "bidirectional"))
      (node (ref "U$7") (pin "P18") (pinfunction "DRAIN18_P18") (pintype "bidirectional"))
      (node (ref "U$7") (pin "P26") (pinfunction "SENSE_P26") (pintype "bidirectional"))
      (node (ref "U$7") (pin "P27") (pinfunction "DRAIN27_P27") (pintype "bidirectional"))
      (node (ref "U$7") (pin "P5") (pinfunction "DRAIN5_P5") (pintype "bidirectional"))
    )
    (net (code "71") (name "Net-(U$7-PROG)") (class "Default")
      (node (ref "R_PROG3") (pin "2") (pinfunction "2_2") (pintype "passive"))
      (node (ref "U$7") (pin "P34") (pinfunction "PROG_P34") (pintype "bidirectional"))
    )
    (net (code "72") (name "Net-(U$7-SET)") (class "Default")
      (node (ref "R_SET3") (pin "1") (pinfunction "1_1") (pintype "passive"))
      (node (ref "U$7") (pin "P3") (pinfunction "SET_P3") (pintype "bidirectional"))
    )
    (net (code "73") (name "Net-(U$7-TIMER)") (class "Default")
      (node (ref "C_TIMER3") (pin "1") (pinfunction "1_1") (pintype "passive"))
      (node (ref "U$7") (pin "P35") (pinfunction "TIMER_P35") (pintype "bidirectional"))
    )
    (net (code "74") (name "Net-(U$8-DRAIN14)") (class "Default")
      (node (ref "R_SENSE4") (pin "2") (pinfunction "2_2") (pintype "passive"))
      (node (ref "U$8") (pin "P$38") (pinfunction "DRAIN38_P$38") (pintype "bidirectional"))
      (node (ref "U$8") (pin "P14") (pinfunction "DRAIN14_P14") (pintype "bidirectional"))
      (node (ref "U$8") (pin "P15") (pinfunction "DRAIN15_P15") (pintype "bidirectional"))
      (node (ref "U$8") (pin "P16") (pinfunction "DRAIN16_P16") (pintype "bidirectional"))
      (node (ref "U$8") (pin "P17") (pinfunction "DRAIN17_P17") (pintype "bidirectional"))
      (node (ref "U$8") (pin "P18") (pinfunction "DRAIN18_P18") (pintype "bidirectional"))
      (node (ref "U$8") (pin "P26") (pinfunction "SENSE_P26") (pintype "bidirectional"))
      (node (ref "U$8") (pin "P27") (pinfunction "DRAIN27_P27") (pintype "bidirectional"))
      (node (ref "U$8") (pin "P5") (pinfunction "DRAIN5_P5") (pintype "bidirectional"))
    )
    (net (code "75") (name "Net-(U$8-PROG)") (class "Default")
      (node (ref "R_PROG4") (pin "2") (pinfunction "2_2") (pintype "passive"))
      (node (ref "U$8") (pin "P34") (pinfunction "PROG_P34") (pintype "bidirectional"))
    )
    (net (code "76") (name "Net-(U$8-SET)") (class "Default")
      (node (ref "R_SET4") (pin "1") (pinfunction "1_1") (pintype "passive"))
      (node (ref "U$8") (pin "P3") (pinfunction "SET_P3") (pintype "bidirectional"))
    )
    (net (code "77") (name "Net-(U$8-TIMER)") (class "Default")
      (node (ref "C_TIMER4") (pin "1") (pinfunction "1_1") (pintype "passive"))
      (node (ref "U$8") (pin "P35") (pinfunction "TIMER_P35") (pintype "bidirectional"))
    )
    (net (code "78") (name "Net-(U$9-DRAIN14)") (class "Default")
      (node (ref "R_SENSE5") (pin "2") (pinfunction "2_2") (pintype "passive"))
      (node (ref "U$9") (pin "P$38") (pinfunction "DRAIN38_P$38") (pintype "bidirectional"))
      (node (ref "U$9") (pin "P14") (pinfunction "DRAIN14_P14") (pintype "bidirectional"))
      (node (ref "U$9") (pin "P15") (pinfunction "DRAIN15_P15") (pintype "bidirectional"))
      (node (ref "U$9") (pin "P16") (pinfunction "DRAIN16_P16") (pintype "bidirectional"))
      (node (ref "U$9") (pin "P17") (pinfunction "DRAIN17_P17") (pintype "bidirectional"))
      (node (ref "U$9") (pin "P18") (pinfunction "DRAIN18_P18") (pintype "bidirectional"))
      (node (ref "U$9") (pin "P26") (pinfunction "SENSE_P26") (pintype "bidirectional"))
      (node (ref "U$9") (pin "P27") (pinfunction "DRAIN27_P27") (pintype "bidirectional"))
      (node (ref "U$9") (pin "P5") (pinfunction "DRAIN5_P5") (pintype "bidirectional"))
    )
    (net (code "79") (name "Net-(U$9-PROG)") (class "Default")
      (node (ref "R_PROG5") (pin "2") (pinfunction "2_2") (pintype "passive"))
      (node (ref "U$9") (pin "P34") (pinfunction "PROG_P34") (pintype "bidirectional"))
    )
    (net (code "80") (name "Net-(U$9-SET)") (class "Default")
      (node (ref "R_SET5") (pin "1") (pinfunction "1_1") (pintype "passive"))
      (node (ref "U$9") (pin "P3") (pinfunction "SET_P3") (pintype "bidirectional"))
    )
    (net (code "81") (name "Net-(U$9-TIMER)") (class "Default")
      (node (ref "C_TIMER5") (pin "1") (pinfunction "1_1") (pintype "passive"))
      (node (ref "U$9") (pin "P35") (pinfunction "TIMER_P35") (pintype "bidirectional"))
    )
    (net (code "82") (name "Net-(U$10-DRAIN14)") (class "Default")
      (node (ref "R_SENSE6") (pin "2") (pinfunction "2_2") (pintype "passive"))
      (node (ref "U$10") (pin "P$38") (pinfunction "DRAIN38_P$38") (pintype "bidirectional"))
      (node (ref "U$10") (pin "P14") (pinfunction "DRAIN14_P14") (pintype "bidirectional"))
      (node (ref "U$10") (pin "P15") (pinfunction "DRAIN15_P15") (pintype "bidirectional"))
      (node (ref "U$10") (pin "P16") (pinfunction "DRAIN16_P16") (pintype "bidirectional"))
      (node (ref "U$10") (pin "P17") (pinfunction "DRAIN17_P17") (pintype "bidirectional"))
      (node (ref "U$10") (pin "P18") (pinfunction "DRAIN18_P18") (pintype "bidirectional"))
      (node (ref "U$10") (pin "P26") (pinfunction "SENSE_P26") (pintype "bidirectional"))
      (node (ref "U$10") (pin "P27") (pinfunction "DRAIN27_P27") (pintype "bidirectional"))
      (node (ref "U$10") (pin "P5") (pinfunction "DRAIN5_P5") (pintype "bidirectional"))
    )
    (net (code "83") (name "Net-(U$10-PROG)") (class "Default")
      (node (ref "R_PROG6") (pin "2") (pinfunction "2_2") (pintype "passive"))
      (node (ref "U$10") (pin "P34") (pinfunction "PROG_P34") (pintype "bidirectional"))
    )
    (net (code "84") (name "Net-(U$10-SET)") (class "Default")
      (node (ref "R_SET6") (pin "1") (pinfunction "1_1") (pintype "passive"))
      (node (ref "U$10") (pin "P3") (pinfunction "SET_P3") (pintype "bidirectional"))
    )
    (net (code "85") (name "Net-(U$10-TIMER)") (class "Default")
      (node (ref "C_TIMER6") (pin "1") (pinfunction "1_1") (pintype "passive"))
      (node (ref "U$10") (pin "P35") (pinfunction "TIMER_P35") (pintype "bidirectional"))
    )
    (net (code "86") (name "Net-(U$11-DRAIN14)") (class "Default")
      (node (ref "R_SENSE7") (pin "2") (pinfunction "2_2") (pintype "passive"))
      (node (ref "U$11") (pin "P$38") (pinfunction "DRAIN38_P$38") (pintype "bidirectional"))
      (node (ref "U$11") (pin "P14") (pinfunction "DRAIN14_P14") (pintype "bidirectional"))
      (node (ref "U$11") (pin "P15") (pinfunction "DRAIN15_P15") (pintype "bidirectional"))
      (node (ref "U$11") (pin "P16") (pinfunction "DRAIN16_P16") (pintype "bidirectional"))
      (node (ref "U$11") (pin "P17") (pinfunction "DRAIN17_P17") (pintype "bidirectional"))
      (node (ref "U$11") (pin "P18") (pinfunction "DRAIN18_P18") (pintype "bidirectional"))
      (node (ref "U$11") (pin "P26") (pinfunction "SENSE_P26") (pintype "bidirectional"))
      (node (ref "U$11") (pin "P27") (pinfunction "DRAIN27_P27") (pintype "bidirectional"))
      (node (ref "U$11") (pin "P5") (pinfunction "DRAIN5_P5") (pintype "bidirectional"))
    )
    (net (code "87") (name "Net-(U$11-PROG)") (class "Default")
      (node (ref "R_PROG7") (pin "2") (pinfunction "2_2") (pintype "passive"))
      (node (ref "U$11") (pin "P34") (pinfunction "PROG_P34") (pintype "bidirectional"))
    )
    (net (code "88") (name "Net-(U$11-SET)") (class "Default")
      (node (ref "R_SET7") (pin "1") (pinfunction "1_1") (pintype "passive"))
      (node (ref "U$11") (pin "P3") (pinfunction "SET_P3") (pintype "bidirectional"))
    )
    (net (code "89") (name "Net-(U$11-TIMER)") (class "Default")
      (node (ref "C_TIMER7") (pin "1") (pinfunction "1_1") (pintype "passive"))
      (node (ref "U$11") (pin "P35") (pinfunction "TIMER_P35") (pintype "bidirectional"))
    )
    (net (code "90") (name "Net-(U$12-DRAIN14)") (class "Default")
      (node (ref "R_SENSE8") (pin "2") (pinfunction "2_2") (pintype "passive"))
      (node (ref "U$12") (pin "P$38") (pinfunction "DRAIN38_P$38") (pintype "bidirectional"))
      (node (ref "U$12") (pin "P14") (pinfunction "DRAIN14_P14") (pintype "bidirectional"))
      (node (ref "U$12") (pin "P15") (pinfunction "DRAIN15_P15") (pintype "bidirectional"))
      (node (ref "U$12") (pin "P16") (pinfunction "DRAIN16_P16") (pintype "bidirectional"))
      (node (ref "U$12") (pin "P17") (pinfunction "DRAIN17_P17") (pintype "bidirectional"))
      (node (ref "U$12") (pin "P18") (pinfunction "DRAIN18_P18") (pintype "bidirectional"))
      (node (ref "U$12") (pin "P26") (pinfunction "SENSE_P26") (pintype "bidirectional"))
      (node (ref "U$12") (pin "P27") (pinfunction "DRAIN27_P27") (pintype "bidirectional"))
      (node (ref "U$12") (pin "P5") (pinfunction "DRAIN5_P5") (pintype "bidirectional"))
    )
    (net (code "91") (name "Net-(U$12-PROG)") (class "Default")
      (node (ref "R_PROG8") (pin "2") (pinfunction "2_2") (pintype "passive"))
      (node (ref "U$12") (pin "P34") (pinfunction "PROG_P34") (pintype "bidirectional"))
    )
    (net (code "92") (name "Net-(U$12-SET)") (class "Default")
      (node (ref "R_SET8") (pin "1") (pinfunction "1_1") (pintype "passive"))
      (node (ref "U$12") (pin "P3") (pinfunction "SET_P3") (pintype "bidirectional"))
    )
    (net (code "93") (name "Net-(U$12-TIMER)") (class "Default")
      (node (ref "C_TIMER8") (pin "1") (pinfunction "1_1") (pintype "passive"))
      (node (ref "U$12") (pin "P35") (pinfunction "TIMER_P35") (pintype "bidirectional"))
    )
    (net (code "94") (name "Net-(U$13-FB)") (class "Default")
      (node (ref "C20") (pin "2") (pinfunction "2_2") (pintype "passive"))
      (node (ref "CSYNC2") (pin "2") (pinfunction "2_2") (pintype "passive"))
      (node (ref "CSYNC3") (pin "1") (pinfunction "1_1") (pintype "passive"))
      (node (ref "JP1") (pin "2") (pinfunction "2_2") (pintype "passive"))
      (node (ref "U$13") (pin "P$5") (pinfunction "FB_P$5") (pintype "bidirectional"))
    )
    (net (code "95") (name "Net-(U$14-FB)") (class "Default")
      (node (ref "C21") (pin "2") (pinfunction "2_2") (pintype "passive"))
      (node (ref "CSYNC4") (pin "2") (pinfunction "2_2") (pintype "passive"))
      (node (ref "CSYNC5") (pin "1") (pinfunction "1_1") (pintype "passive"))
      (node (ref "JP2") (pin "2") (pinfunction "2_2") (pintype "passive"))
      (node (ref "U$14") (pin "P$5") (pinfunction "FB_P$5") (pintype "bidirectional"))
    )
    (net (code "96") (name "Net-(U$14-INTV)") (class "Default")
      (node (ref "CINTV2") (pin "1") (pinfunction "1_1") (pintype "passive"))
      (node (ref "U$14") (pin "P$6") (pinfunction "INTV_P$6") (pintype "bidirectional"))
    )
    (net (code "97") (name "Net-(U$14-MODE)") (class "Default")
      (node (ref "RSYNC2") (pin "1") (pinfunction "1_1") (pintype "passive"))
      (node (ref "U$14") (pin "P$7") (pinfunction "MODE_P$7") (pintype "bidirectional"))
    )
    (net (code "98") (name "Net-(U$15-PadSBWTCK)") (class "Default")
      (node (ref "U$15") (pin "SBWTCK") (pinfunction "SBWTCK_SBWTCK") (pintype "bidirectional"))
      (node (ref "U$16") (pin "SBWTCK") (pinfunction "SBWTCK_SBWTCK") (pintype "bidirectional"))
    )
    (net (code "99") (name "Net-(U$16-P2.0_TXD)") (class "Default")
      (node (ref "U$15") (pin "P2.0_TXD") (pinfunction "P2.0_TXD_P2.0_TXD") (pintype "bidirectional"))
      (node (ref "U$16") (pin "3") (pinfunction "P2.0_TXD_3") (pintype "bidirectional"))
    )
    (net (code "100") (name "Net-(U$16-P2.1_RXD)") (class "Default")
      (node (ref "U$15") (pin "P2.1_RXD") (pinfunction "P2.1_RXD_P2.1_RXD") (pintype "bidirectional"))
      (node (ref "U$16") (pin "4") (pinfunction "P2.1_RXD_4") (pintype "bidirectional"))
    )
    (net (code "101") (name "Net-(U$16-P3.4_GPIO_DEBUG)") (class "Default")
      (node (ref "U$15") (pin "P3.4_GPIO_DEBUG") (pinfunction "P3.4_GPIO_DEBUG_P3.4_GPIO_DEBUG") (pintype "bidirectional"))
      (node (ref "U$16") (pin "7") (pinfunction "P3.4_GPIO_DEBUG_7") (pintype "bidirectional"))
    )
    (net (code "102") (name "Net-(U$16-P3.5_GPIO_DEBUG)") (class "Default")
      (node (ref "U$15") (pin "P3.5_GPIO_DEBUG") (pinfunction "P3.5_GPIO_DEBUG_P3.5_GPIO_DEBUG") (pintype "bidirectional"))
      (node (ref "U$16") (pin "8") (pinfunction "P3.5_GPIO_DEBUG_8") (pintype "bidirectional"))
    )
    (net (code "103") (name "Net-(U$16-SBWTDIO)") (class "Default")
      (node (ref "U$15") (pin "SBWTDIO") (pinfunction "SBWTDIO_SBWTDIO") (pintype "bidirectional"))
      (node (ref "U$16") (pin "2") (pinfunction "SBWTDIO_2") (pintype "bidirectional"))
    )
    (net (code "104") (name "PPT_EN") (class "Default")
      (node (ref "D1") (pin "A") (pinfunction "A_A") (pintype "passive"))
      (node (ref "J2") (pin "1") (pinfunction "1_1") (pintype "passive"))
      (node (ref "R10") (pin "2") (pinfunction "2_2") (pintype "passive"))
      (node (ref "U$1") (pin "P33") (pinfunction "EN_P33") (pintype "bidirectional"))
      (node (ref "U$15") (pin "P7.3_GPIO") (pinfunction "P7.3_GPIO_P7.3_GPIO") (pintype "bidirectional"))
    )
    (net (code "105") (name "PPT_IMON") (class "Default")
      (node (ref "R_AN9") (pin "2") (pinfunction "2_2") (pintype "passive"))
      (node (ref "R_IMON") (pin "2") (pinfunction "2_2") (pintype "passive"))
      (node (ref "U$1") (pin "P2") (pinfunction "IMON_P2") (pintype "bidirectional"))
    )
    (net (code "106") (name "PPT_VOUT") (class "Default")
      (node (ref "C11") (pin "1") (pinfunction "1_1") (pintype "passive"))
      (node (ref "C12") (pin "1") (pinfunction "1_1") (pintype "passive"))
      (node (ref "C_OUT") (pin "1") (pinfunction "1_1") (pintype "passive"))
      (node (ref "U$1") (pin "P10") (pinfunction "OUT10_P10") (pintype "bidirectional"))
      (node (ref "U$1") (pin "P11") (pinfunction "OUT11_P11") (pintype "bidirectional"))
      (node (ref "U$1") (pin "P12") (pinfunction "OUT12_P12") (pintype "bidirectional"))
      (node (ref "U$1") (pin "P13") (pinfunction "OUT13_P13") (pintype "bidirectional"))
      (node (ref "U$1") (pin "P19") (pinfunction "OUT19_P19") (pintype "bidirectional"))
      (node (ref "U$1") (pin "P20") (pinfunction "OUT20_P20") (pintype "bidirectional"))
      (node (ref "U$1") (pin "P21") (pinfunction "OUT21_P21") (pintype "bidirectional"))
      (node (ref "U$1") (pin "P22") (pinfunction "OUT22_P22") (pintype "bidirectional"))
      (node (ref "U$1") (pin "P23") (pinfunction "OUT23_P23") (pintype "bidirectional"))
      (node (ref "U$1") (pin "P24") (pinfunction "OUT24_P24") (pintype "bidirectional"))
      (node (ref "U$1") (pin "P6") (pinfunction "OUT6_P6") (pintype "bidirectional"))
      (node (ref "U$1") (pin "P7") (pinfunction "OUT7_P7") (pintype "bidirectional"))
      (node (ref "U$1") (pin "P8") (pinfunction "OUT8_P8") (pintype "bidirectional"))
      (node (ref "U$1") (pin "P9") (pinfunction "OUT9_P9") (pintype "bidirectional"))
      (node (ref "U$2") (pin "P$10") (pinfunction "PPT_VBAT_P$10") (pintype "bidirectional"))
      (node (ref "U$2") (pin "P$12") (pinfunction "PPT_VBAT_P$12") (pintype "bidirectional"))
      (node (ref "U$2") (pin "P$13") (pinfunction "PPT_VBAT_P$13") (pintype "bidirectional"))
      (node (ref "U$2") (pin "P$15") (pinfunction "PPT_VBAT_P$15") (pintype "bidirectional"))
      (node (ref "U$2") (pin "P$2") (pinfunction "PPT_VBAT_P$2") (pintype "bidirectional"))
      (node (ref "U$2") (pin "P$4") (pinfunction "PPT_VBAT_P$4") (pintype "bidirectional"))
      (node (ref "U$2") (pin "P$5") (pinfunction "PPT_VBAT_P$5") (pintype "bidirectional"))
      (node (ref "U$2") (pin "P$7") (pinfunction "PPT_VBAT_P$7") (pintype "bidirectional"))
    )
    (net (code "107") (name "REACTION_EN") (class "Default")
      (node (ref "D7") (pin "A") (pinfunction "A_A") (pintype "passive"))
      (node (ref "J2") (pin "5") (pinfunction "5_5") (pintype "passive"))
      (node (ref "R6") (pin "2") (pinfunction "2_2") (pintype "passive"))
      (node (ref "U$10") (pin "P33") (pinfunction "EN_P33") (pintype "bidirectional"))
      (node (ref "U$15") (pin "P4.2_GPIO") (pinfunction "P4.2_GPIO_P4.2_GPIO") (pintype "bidirectional"))
    )
    (net (code "108") (name "REACTION_IMON") (class "Default")
      (node (ref "R_AN5") (pin "2") (pinfunction "2_2") (pintype "passive"))
      (node (ref "R_IMON6") (pin "2") (pinfunction "2_2") (pintype "passive"))
      (node (ref "U$10") (pin "P2") (pinfunction "IMON_P2") (pintype "bidirectional"))
    )
    (net (code "109") (name "REACTION_VOUT") (class "Default")
      (node (ref "C_OUT6") (pin "1") (pinfunction "1_1") (pintype "passive"))
      (node (ref "U$10") (pin "P10") (pinfunction "OUT10_P10") (pintype "bidirectional"))
      (node (ref "U$10") (pin "P11") (pinfunction "OUT11_P11") (pintype "bidirectional"))
      (node (ref "U$10") (pin "P12") (pinfunction "OUT12_P12") (pintype "bidirectional"))
      (node (ref "U$10") (pin "P13") (pinfunction "OUT13_P13") (pintype "bidirectional"))
      (node (ref "U$10") (pin "P19") (pinfunction "OUT19_P19") (pintype "bidirectional"))
      (node (ref "U$10") (pin "P20") (pinfunction "OUT20_P20") (pintype "bidirectional"))
      (node (ref "U$10") (pin "P21") (pinfunction "OUT21_P21") (pintype "bidirectional"))
      (node (ref "U$10") (pin "P22") (pinfunction "OUT22_P22") (pintype "bidirectional"))
      (node (ref "U$10") (pin "P23") (pinfunction "OUT23_P23") (pintype "bidirectional"))
      (node (ref "U$10") (pin "P24") (pinfunction "OUT24_P24") (pintype "bidirectional"))
      (node (ref "U$10") (pin "P6") (pinfunction "OUT6_P6") (pintype "bidirectional"))
      (node (ref "U$10") (pin "P7") (pinfunction "OUT7_P7") (pintype "bidirectional"))
      (node (ref "U$10") (pin "P8") (pinfunction "OUT8_P8") (pintype "bidirectional"))
      (node (ref "U$10") (pin "P9") (pinfunction "OUT9_P9") (pintype "bidirectional"))
      (node (ref "U$2") (pin "P$81") (pinfunction "ADCS2_VBAT_P$81") (pintype "bidirectional"))
      (node (ref "U$2") (pin "P$83") (pinfunction "ADCS2_VBAT_P$83") (pintype "bidirectional"))
    )
    (net (code "110") (name "VCC") (class "Default")
      (node (ref "C10") (pin "1") (pinfunction "1_1") (pintype "passive"))
      (node (ref "C13") (pin "1") (pinfunction "1_1") (pintype "passive"))
      (node (ref "C3") (pin "1") (pinfunction "1_1") (pintype "passive"))
      (node (ref "C4") (pin "1") (pinfunction "1_1") (pintype "passive"))
      (node (ref "C5") (pin "1") (pinfunction "1_1") (pintype "passive"))
      (node (ref "C6") (pin "1") (pinfunction "1_1") (pintype "passive"))
      (node (ref "C7") (pin "1") (pinfunction "1_1") (pintype "passive"))
      (node (ref "C8") (pin "1") (pinfunction "1_1") (pintype "passive"))
      (node (ref "C9") (pin "1") (pinfunction "1_1") (pintype "passive"))
      (node (ref "CIN2") (pin "1") (pinfunction "1_1") (pintype "passive"))
      (node (ref "CIN4") (pin "1") (pinfunction "1_1") (pintype "passive"))
      (node (ref "CV1") (pin "1") (pinfunction "1_1") (pintype "passive"))
      (node (ref "CV2") (pin "1") (pinfunction "1_1") (pintype "passive"))
      (node (ref "CV3") (pin "1") (pinfunction "1_1") (pintype "passive"))
      (node (ref "CV4") (pin "1") (pinfunction "1_1") (pintype "passive"))
      (node (ref "CV5") (pin "1") (pinfunction "1_1") (pintype "passive"))
      (node (ref "CV6") (pin "1") (pinfunction "1_1") (pintype "passive"))
      (node (ref "IC1") (pin "1") (pinfunction "IN_1") (pintype "input"))
      (node (ref "IC2") (pin "1") (pinfunction "IN_1") (pintype "input"))
      (node (ref "R_SENSE") (pin "1") (pinfunction "1_1") (pintype "passive"))
      (node (ref "R_SENSE3") (pin "1") (pinfunction "1_1") (pintype "passive"))
      (node (ref "R_SENSE4") (pin "1") (pinfunction "1_1") (pintype "passive"))
      (node (ref "R_SENSE5") (pin "1") (pinfunction "1_1") (pintype "passive"))
      (node (ref "R_SENSE6") (pin "1") (pinfunction "1_1") (pintype "passive"))
      (node (ref "R_SENSE7") (pin "1") (pinfunction "1_1") (pintype "passive"))
      (node (ref "R_SENSE8") (pin "1") (pinfunction "1_1") (pintype "passive"))
      (node (ref "R_SET") (pin "2") (pinfunction "2_2") (pintype "passive"))
      (node (ref "R_SET3") (pin "2") (pinfunction "2_2") (pintype "passive"))
      (node (ref "R_SET4") (pin "2") (pinfunction "2_2") (pintype "passive"))
      (node (ref "R_SET5") (pin "2") (pinfunction "2_2") (pintype "passive"))
      (node (ref "R_SET6") (pin "2") (pinfunction "2_2") (pintype "passive"))
      (node (ref "R_SET7") (pin "2") (pinfunction "2_2") (pintype "passive"))
      (node (ref "R_SET8") (pin "2") (pinfunction "2_2") (pintype "passive"))
      (node (ref "U$1") (pin "P29") (pinfunction "VCC_P29") (pintype "bidirectional"))
      (node (ref "U$10") (pin "P29") (pinfunction "VCC_P29") (pintype "bidirectional"))
      (node (ref "U$11") (pin "P29") (pinfunction "VCC_P29") (pintype "bidirectional"))
      (node (ref "U$12") (pin "P29") (pinfunction "VCC_P29") (pintype "bidirectional"))
      (node (ref "U$13") (pin "P$2") (pinfunction "VIN_P$2") (pintype "bidirectional"))
      (node (ref "U$14") (pin "P$2") (pinfunction "VIN_P$2") (pintype "bidirectional"))
      (node (ref "U$2") (pin "P$18") (pinfunction "DISTRI_VBAT_P$18") (pintype "bidirectional"))
      (node (ref "U$2") (pin "P$20") (pinfunction "DISTRI_VBAT_P$20") (pintype "bidirectional"))
      (node (ref "U$2") (pin "P$21") (pinfunction "DISTRI_VBAT_P$21") (pintype "bidirectional"))
      (node (ref "U$2") (pin "P$23") (pinfunction "DISTRI_VBAT_P$23") (pintype "bidirectional"))
      (node (ref "U$2") (pin "P$26") (pinfunction "DISTRI_VBAT_P$26") (pintype "bidirectional"))
      (node (ref "U$2") (pin "P$28") (pinfunction "DISTRI_VBAT_P$28") (pintype "bidirectional"))
      (node (ref "U$2") (pin "P$29") (pinfunction "DISTRI_VBAT_P$29") (pintype "bidirectional"))
      (node (ref "U$2") (pin "P$31") (pinfunction "DISTRI_VBAT_P$31") (pintype "bidirectional"))
      (node (ref "U$7") (pin "P29") (pinfunction "VCC_P29") (pintype "bidirectional"))
      (node (ref "U$8") (pin "P29") (pinfunction "VCC_P29") (pintype "bidirectional"))
      (node (ref "U$9") (pin "P29") (pinfunction "VCC_P29") (pintype "bidirectional"))
    )
    (net (code "111") (name "unconnected-(IC1-NC{slash}FB-Pad4)") (class "Default")
      (node (ref "IC1") (pin "4") (pinfunction "NC/FB_4") (pintype "passive"))
    )
    (net (code "112") (name "unconnected-(IC2-NC{slash}FB-Pad4)") (class "Default")
      (node (ref "IC2") (pin "4") (pinfunction "NC/FB_4") (pintype "passive"))
    )
    (net (code "113") (name "unconnected-(U$1-FLTB-PadP30)") (class "Default")
      (node (ref "U$1") (pin "P30") (pinfunction "FLTB_P30") (pintype "bidirectional"))
    )
    (net (code "114") (name "unconnected-(U$1-GATE-PadP25)") (class "Default")
      (node (ref "U$1") (pin "P25") (pinfunction "GATE_P25") (pintype "bidirectional"))
    )
    (net (code "115") (name "unconnected-(U$1-PGB-PadP31)") (class "Default")
      (node (ref "U$1") (pin "P31") (pinfunction "PGB_P31") (pintype "bidirectional"))
    )
    (net (code "116") (name "unconnected-(U$2-BDOT_I2C_SCL-PadP$90)") (class "Default")
      (node (ref "U$2") (pin "P$90") (pinfunction "BDOT_I2C_SCL_P$90") (pintype "bidirectional"))
    )
    (net (code "117") (name "unconnected-(U$2-BDOT_I2C_SDA-PadP$89)") (class "Default")
      (node (ref "U$2") (pin "P$89") (pinfunction "BDOT_I2C_SDA_P$89") (pintype "bidirectional"))
    )
    (net (code "118") (name "unconnected-(U$2-ESTIMAT_I2C_SCL-PadP$70)") (class "Default")
      (node (ref "U$2") (pin "P$70") (pinfunction "ESTIMAT_I2C_SCL_P$70") (pintype "bidirectional"))
    )
    (net (code "119") (name "unconnected-(U$2-ESTIMAT_I2C_SDA-PadP$69)") (class "Default")
      (node (ref "U$2") (pin "P$69") (pinfunction "ESTIMAT_I2C_SDA_P$69") (pintype "bidirectional"))
    )
    (net (code "120") (name "unconnected-(U$2-MAG1_PWM-PadP$73)") (class "Default")
      (node (ref "U$2") (pin "P$73") (pinfunction "MAG1_PWM_P$73") (pintype "bidirectional"))
    )
    (net (code "121") (name "unconnected-(U$2-MAG2_PWM-PadP$74)") (class "Default")
      (node (ref "U$2") (pin "P$74") (pinfunction "MAG2_PWM_P$74") (pintype "bidirectional"))
    )
    (net (code "122") (name "unconnected-(U$2-MAG3_PWM-PadP$75)") (class "Default")
      (node (ref "U$2") (pin "P$75") (pinfunction "MAG3_PWM_P$75") (pintype "bidirectional"))
    )
    (net (code "123") (name "unconnected-(U$2-PadP$33)") (class "Default")
      (node (ref "U$2") (pin "P$33") (pinfunction "P$33_P$33") (pintype "bidirectional"))
    )
    (net (code "124") (name "unconnected-(U$2-PadP$34)") (class "Default")
      (node (ref "U$2") (pin "P$34") (pinfunction "P$34_P$34") (pintype "bidirectional"))
    )
    (net (code "125") (name "unconnected-(U$2-PadP$35)") (class "Default")
      (node (ref "U$2") (pin "P$35") (pinfunction "P$35_P$35") (pintype "bidirectional"))
    )
    (net (code "126") (name "unconnected-(U$2-PadP$36)") (class "Default")
      (node (ref "U$2") (pin "P$36") (pinfunction "P$36_P$36") (pintype "bidirectional"))
    )
    (net (code "127") (name "unconnected-(U$2-PadP$37)") (class "Default")
      (node (ref "U$2") (pin "P$37") (pinfunction "P$37_P$37") (pintype "bidirectional"))
    )
    (net (code "128") (name "unconnected-(U$2-PadP$38)") (class "Default")
      (node (ref "U$2") (pin "P$38") (pinfunction "P$38_P$38") (pintype "bidirectional"))
    )
    (net (code "129") (name "unconnected-(U$2-PadP$39)") (class "Default")
      (node (ref "U$2") (pin "P$39") (pinfunction "P$39_P$39") (pintype "bidirectional"))
    )
    (net (code "130") (name "unconnected-(U$2-PadP$40)") (class "Default")
      (node (ref "U$2") (pin "P$40") (pinfunction "P$40_P$40") (pintype "bidirectional"))
    )
    (net (code "131") (name "unconnected-(U$2-PadP$41)") (class "Default")
      (node (ref "U$2") (pin "P$41") (pinfunction "P$41_P$41") (pintype "bidirectional"))
    )
    (net (code "132") (name "unconnected-(U$2-PadP$42)") (class "Default")
      (node (ref "U$2") (pin "P$42") (pinfunction "P$42_P$42") (pintype "bidirectional"))
    )
    (net (code "133") (name "unconnected-(U$2-PadP$43)") (class "Default")
      (node (ref "U$2") (pin "P$43") (pinfunction "P$43_P$43") (pintype "bidirectional"))
    )
    (net (code "134") (name "unconnected-(U$2-PadP$44)") (class "Default")
      (node (ref "U$2") (pin "P$44") (pinfunction "P$44_P$44") (pintype "bidirectional"))
    )
    (net (code "135") (name "unconnected-(U$2-PadP$48)") (class "Default")
      (node (ref "U$2") (pin "P$48") (pinfunction "P$48_P$48") (pintype "bidirectional"))
    )
    (net (code "136") (name "unconnected-(U$2-PadP$52)") (class "Default")
      (node (ref "U$2") (pin "P$52") (pinfunction "P$52_P$52") (pintype "bidirectional"))
    )
    (net (code "137") (name "unconnected-(U$2-PadP$56)") (class "Default")
      (node (ref "U$2") (pin "P$56") (pinfunction "P$56_P$56") (pintype "bidirectional"))
    )
    (net (code "138") (name "unconnected-(U$2-PadP$60)") (class "Default")
      (node (ref "U$2") (pin "P$60") (pinfunction "P$60_P$60") (pintype "bidirectional"))
    )
    (net (code "139") (name "unconnected-(U$2-PadP$61)") (class "Default")
      (node (ref "U$2") (pin "P$61") (pinfunction "P$61_P$61") (pintype "bidirectional"))
    )
    (net (code "140") (name "unconnected-(U$2-PadP$62)") (class "Default")
      (node (ref "U$2") (pin "P$62") (pinfunction "P$62_P$62") (pintype "bidirectional"))
    )
    (net (code "141") (name "unconnected-(U$2-PadP$63)") (class "Default")
      (node (ref "U$2") (pin "P$63") (pinfunction "P$63_P$63") (pintype "bidirectional"))
    )
    (net (code "142") (name "unconnected-(U$2-PadP$64)") (class "Default")
      (node (ref "U$2") (pin "P$64") (pinfunction "P$64_P$64") (pintype "bidirectional"))
    )
    (net (code "143") (name "unconnected-(U$2-PadP$65)") (class "Default")
      (node (ref "U$2") (pin "P$65") (pinfunction "P$65_P$65") (pintype "bidirectional"))
    )
    (net (code "144") (name "unconnected-(U$2-PadP$66)") (class "Default")
      (node (ref "U$2") (pin "P$66") (pinfunction "P$66_P$66") (pintype "bidirectional"))
    )
    (net (code "145") (name "unconnected-(U$2-PadP$67)") (class "Default")
      (node (ref "U$2") (pin "P$67") (pinfunction "P$67_P$67") (pintype "bidirectional"))
    )
    (net (code "146") (name "unconnected-(U$2-PadP$68)") (class "Default")
      (node (ref "U$2") (pin "P$68") (pinfunction "P$68_P$68") (pintype "bidirectional"))
    )
    (net (code "147") (name "unconnected-(U$2-PadP$71)") (class "Default")
      (node (ref "U$2") (pin "P$71") (pinfunction "P$71_P$71") (pintype "bidirectional"))
    )
    (net (code "148") (name "unconnected-(U$2-PadP$72)") (class "Default")
      (node (ref "U$2") (pin "P$72") (pinfunction "P$72_P$72") (pintype "bidirectional"))
    )
    (net (code "149") (name "unconnected-(U$2-PadP$76)") (class "Default")
      (node (ref "U$2") (pin "P$76") (pinfunction "P$76_P$76") (pintype "bidirectional"))
    )
    (net (code "150") (name "unconnected-(U$2-PadP$91)") (class "Default")
      (node (ref "U$2") (pin "P$91") (pinfunction "P$91_P$91") (pintype "bidirectional"))
    )
    (net (code "151") (name "unconnected-(U$2-PadP$92)") (class "Default")
      (node (ref "U$2") (pin "P$92") (pinfunction "P$92_P$92") (pintype "bidirectional"))
    )
    (net (code "152") (name "unconnected-(U$2-PadP$95)") (class "Default")
      (node (ref "U$2") (pin "P$95") (pinfunction "P$95_P$95") (pintype "bidirectional"))
    )
    (net (code "153") (name "unconnected-(U$2-PadP$96)") (class "Default")
      (node (ref "U$2") (pin "P$96") (pinfunction "P$96_P$96") (pintype "bidirectional"))
    )
    (net (code "154") (name "unconnected-(U$5-FLTB-PadP30)") (class "Default")
      (node (ref "U$5") (pin "P30") (pinfunction "FLTB_P30") (pintype "bidirectional"))
    )
    (net (code "155") (name "unconnected-(U$5-GATE-PadP25)") (class "Default")
      (node (ref "U$5") (pin "P25") (pinfunction "GATE_P25") (pintype "bidirectional"))
    )
    (net (code "156") (name "unconnected-(U$5-PGB-PadP31)") (class "Default")
      (node (ref "U$5") (pin "P31") (pinfunction "PGB_P31") (pintype "bidirectional"))
    )
    (net (code "157") (name "unconnected-(U$6-FLTB-PadP30)") (class "Default")
      (node (ref "U$6") (pin "P30") (pinfunction "FLTB_P30") (pintype "bidirectional"))
    )
    (net (code "158") (name "unconnected-(U$6-GATE-PadP25)") (class "Default")
      (node (ref "U$6") (pin "P25") (pinfunction "GATE_P25") (pintype "bidirectional"))
    )
    (net (code "159") (name "unconnected-(U$6-PGB-PadP31)") (class "Default")
      (node (ref "U$6") (pin "P31") (pinfunction "PGB_P31") (pintype "bidirectional"))
    )
    (net (code "160") (name "unconnected-(U$7-FLTB-PadP30)") (class "Default")
      (node (ref "U$7") (pin "P30") (pinfunction "FLTB_P30") (pintype "bidirectional"))
    )
    (net (code "161") (name "unconnected-(U$7-GATE-PadP25)") (class "Default")
      (node (ref "U$7") (pin "P25") (pinfunction "GATE_P25") (pintype "bidirectional"))
    )
    (net (code "162") (name "unconnected-(U$7-PGB-PadP31)") (class "Default")
      (node (ref "U$7") (pin "P31") (pinfunction "PGB_P31") (pintype "bidirectional"))
    )
    (net (code "163") (name "unconnected-(U$8-FLTB-PadP30)") (class "Default")
      (node (ref "U$8") (pin "P30") (pinfunction "FLTB_P30") (pintype "bidirectional"))
    )
    (net (code "164") (name "unconnected-(U$8-GATE-PadP25)") (class "Default")
      (node (ref "U$8") (pin "P25") (pinfunction "GATE_P25") (pintype "bidirectional"))
    )
    (net (code "165") (name "unconnected-(U$8-PGB-PadP31)") (class "Default")
      (node (ref "U$8") (pin "P31") (pinfunction "PGB_P31") (pintype "bidirectional"))
    )
    (net (code "166") (name "unconnected-(U$9-FLTB-PadP30)") (class "Default")
      (node (ref "U$9") (pin "P30") (pinfunction "FLTB_P30") (pintype "bidirectional"))
    )
    (net (code "167") (name "unconnected-(U$9-GATE-PadP25)") (class "Default")
      (node (ref "U$9") (pin "P25") (pinfunction "GATE_P25") (pintype "bidirectional"))
    )
    (net (code "168") (name "unconnected-(U$9-PGB-PadP31)") (class "Default")
      (node (ref "U$9") (pin "P31") (pinfunction "PGB_P31") (pintype "bidirectional"))
    )
    (net (code "169") (name "unconnected-(U$10-FLTB-PadP30)") (class "Default")
      (node (ref "U$10") (pin "P30") (pinfunction "FLTB_P30") (pintype "bidirectional"))
    )
    (net (code "170") (name "unconnected-(U$10-GATE-PadP25)") (class "Default")
      (node (ref "U$10") (pin "P25") (pinfunction "GATE_P25") (pintype "bidirectional"))
    )
    (net (code "171") (name "unconnected-(U$10-PGB-PadP31)") (class "Default")
      (node (ref "U$10") (pin "P31") (pinfunction "PGB_P31") (pintype "bidirectional"))
    )
    (net (code "172") (name "unconnected-(U$11-FLTB-PadP30)") (class "Default")
      (node (ref "U$11") (pin "P30") (pinfunction "FLTB_P30") (pintype "bidirectional"))
    )
    (net (code "173") (name "unconnected-(U$11-GATE-PadP25)") (class "Default")
      (node (ref "U$11") (pin "P25") (pinfunction "GATE_P25") (pintype "bidirectional"))
    )
    (net (code "174") (name "unconnected-(U$11-PGB-PadP31)") (class "Default")
      (node (ref "U$11") (pin "P31") (pinfunction "PGB_P31") (pintype "bidirectional"))
    )
    (net (code "175") (name "unconnected-(U$12-FLTB-PadP30)") (class "Default")
      (node (ref "U$12") (pin "P30") (pinfunction "FLTB_P30") (pintype "bidirectional"))
    )
    (net (code "176") (name "unconnected-(U$12-GATE-PadP25)") (class "Default")
      (node (ref "U$12") (pin "P25") (pinfunction "GATE_P25") (pintype "bidirectional"))
    )
    (net (code "177") (name "unconnected-(U$12-PGB-PadP31)") (class "Default")
      (node (ref "U$12") (pin "P31") (pinfunction "PGB_P31") (pintype "bidirectional"))
    )
    (net (code "178") (name "unconnected-(U$13-PGOOD-PadP$4)") (class "Default")
      (node (ref "U$13") (pin "P$4") (pinfunction "PGOOD_P$4") (pintype "bidirectional"))
    )
    (net (code "179") (name "unconnected-(U$14-PGOOD-PadP$4)") (class "Default")
      (node (ref "U$14") (pin "P$4") (pinfunction "PGOOD_P$4") (pintype "bidirectional"))
    )
    (net (code "180") (name "unconnected-(U$15-P2.3_SPI-CS2-PadP2.4_SPI-CS2)") (class "Default")
      (node (ref "U$15") (pin "P2.4_SPI-CS2") (pinfunction "P2.3_SPI-CS2_P2.4_SPI-CS2") (pintype "bidirectional"))
    )
    (net (code "181") (name "unconnected-(U$15-PadP1.5_A5)") (class "Default")
      (node (ref "U$15") (pin "P1.5_A5") (pinfunction "P1.5_A5_P1.5_A5") (pintype "bidirectional"))
    )
    (net (code "182") (name "unconnected-(U$15-PadP2.2_GPIO{slash}PWM)") (class "Default")
      (node (ref "U$15") (pin "P2.2_GPIO/PWM") (pinfunction "P2.2_GPIO/PWM_P2.2_GPIO/PWM") (pintype "bidirectional"))
    )
    (net (code "183") (name "unconnected-(U$15-PadP2.6_GPIO{slash}PWM)") (class "Default")
      (node (ref "U$15") (pin "P2.6_GPIO/PWM") (pinfunction "P2.6_GPIO/PWM_P2.6_GPIO/PWM") (pintype "bidirectional"))
    )
    (net (code "184") (name "unconnected-(U$15-PadP2.7_SPI-CS3)") (class "Default")
      (node (ref "U$15") (pin "P2.7_SPI-CS3") (pinfunction "P2.7_SPI-CS3_P2.7_SPI-CS3") (pintype "bidirectional"))
    )
    (net (code "185") (name "unconnected-(U$15-PadP5.0_I2C-SDA-1)") (class "Default")
      (node (ref "U$15") (pin "P5.0_I2C-SDA-1") (pinfunction "P5.0_I2C-SDA-1_P5.0_I2C-SDA-1") (pintype "bidirectional"))
    )
    (net (code "186") (name "unconnected-(U$15-PadP5.1_I2C-SCL-1)") (class "Default")
      (node (ref "U$15") (pin "P5.1_I2C-SCL-1") (pinfunction "P5.1_I2C-SCL-1_P5.1_I2C-SCL-1") (pintype "bidirectional"))
    )
    (net (code "187") (name "unconnected-(U$15-PadP5.4_SPI-MOSI)") (class "Default")
      (node (ref "U$15") (pin "P5.4_SPI-MOSI") (pinfunction "P5.4_SPI-MOSI_P5.4_SPI-MOSI") (pintype "bidirectional"))
    )
    (net (code "188") (name "unconnected-(U$15-PadP5.5_SPI-MISO)") (class "Default")
      (node (ref "U$15") (pin "P5.5_SPI-MISO") (pinfunction "P5.5_SPI-MISO_P5.5_SPI-MISO") (pintype "bidirectional"))
    )
    (net (code "189") (name "unconnected-(U$15-PadP5.6_SPI-CLK)") (class "Default")
      (node (ref "U$15") (pin "P5.6_SPI-CLK") (pinfunction "P5.6_SPI-CLK_P5.6_SPI-CLK") (pintype "bidirectional"))
    )
    (net (code "190") (name "unconnected-(U$15-PadP7.0_I2C-SDA-2)") (class "Default")
      (node (ref "U$15") (pin "P7.0_I2C-SDA-2") (pinfunction "P7.0_I2C-SDA-2_P7.0_I2C-SDA-2") (pintype "bidirectional"))
    )
    (net (code "191") (name "unconnected-(U$15-PadP7.1_I2C-SCL-2)") (class "Default")
      (node (ref "U$15") (pin "P7.1_I2C-SCL-2") (pinfunction "P7.1_I2C-SCL-2_P7.1_I2C-SCL-2") (pintype "bidirectional"))
    )
  )
)
